# Sobel_FPGA_Block_1.net
KiCad netlist of a schematic drawn in Altium Designer
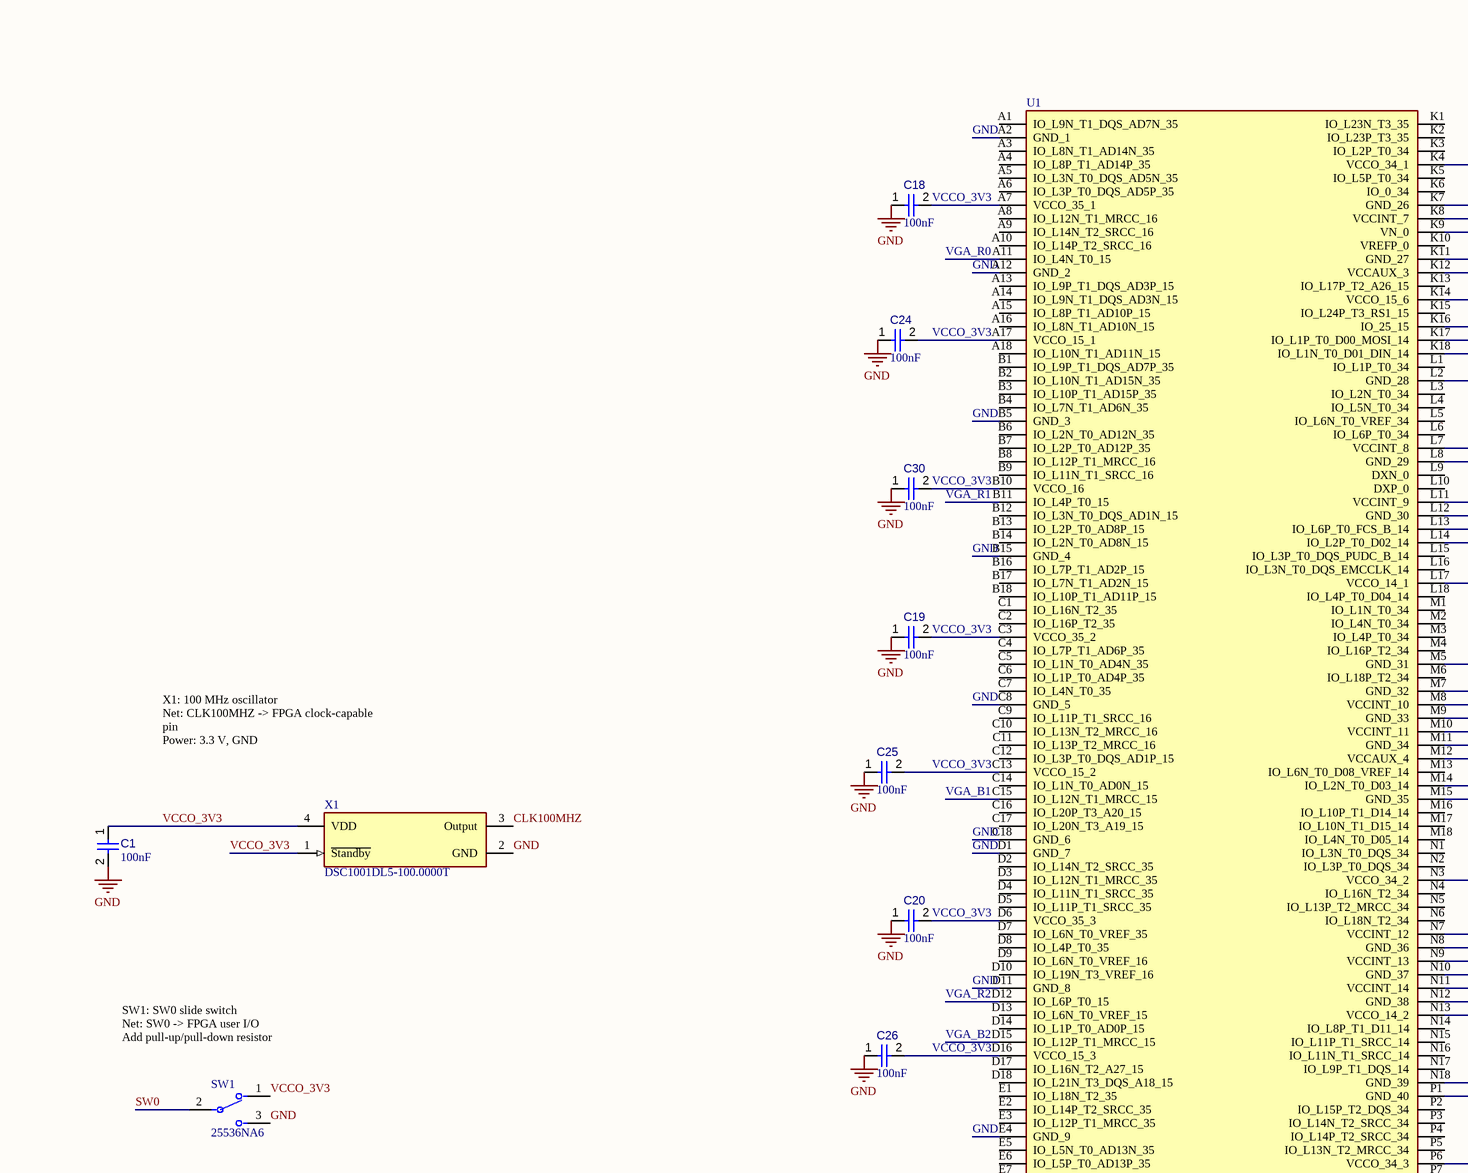
[diagram p0: Sobel_FPGA_Block (1).SchDoc, top left]
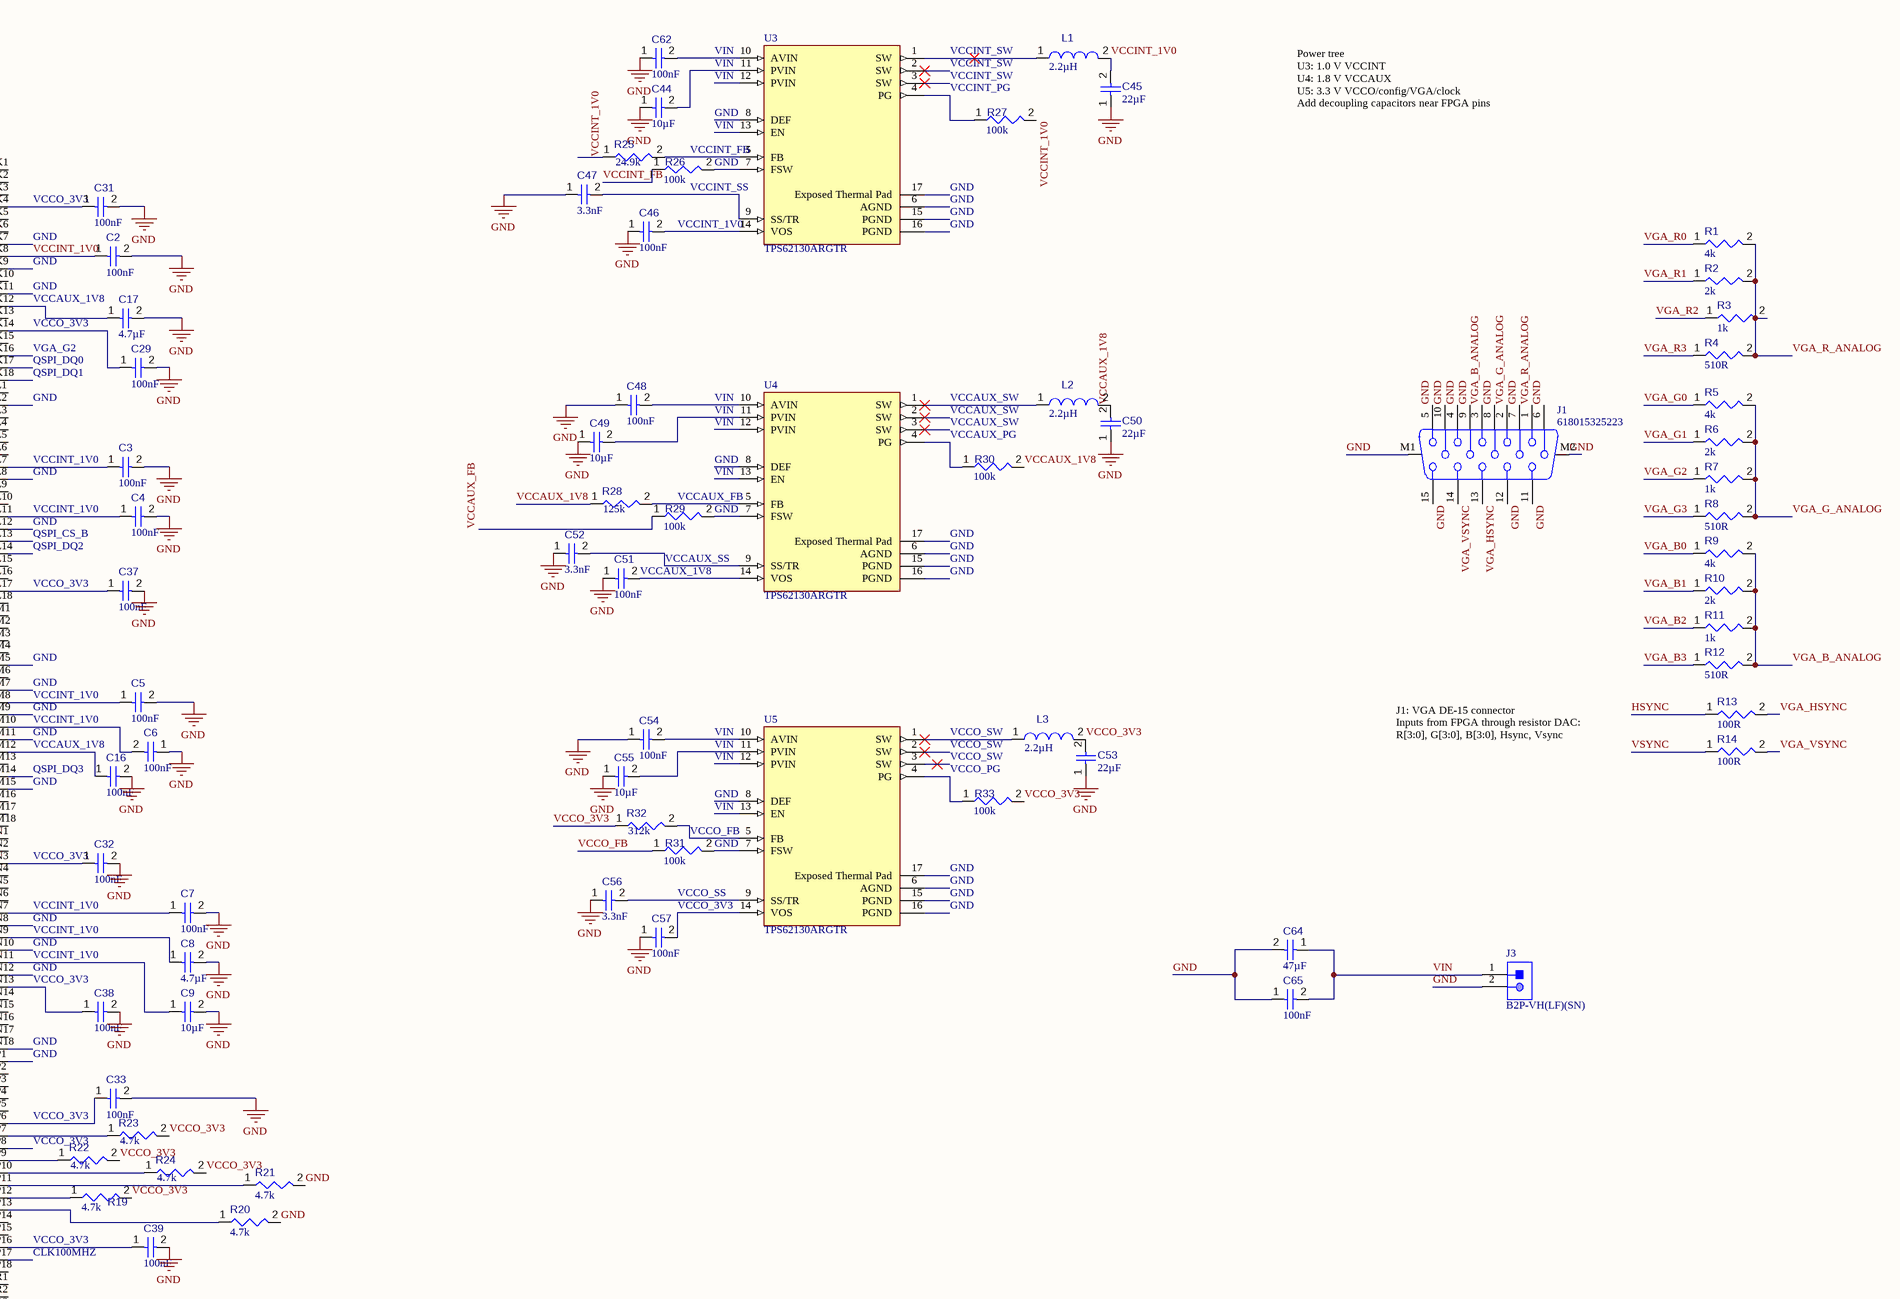
[diagram p1: Sobel_FPGA_Block (1).SchDoc, top right]
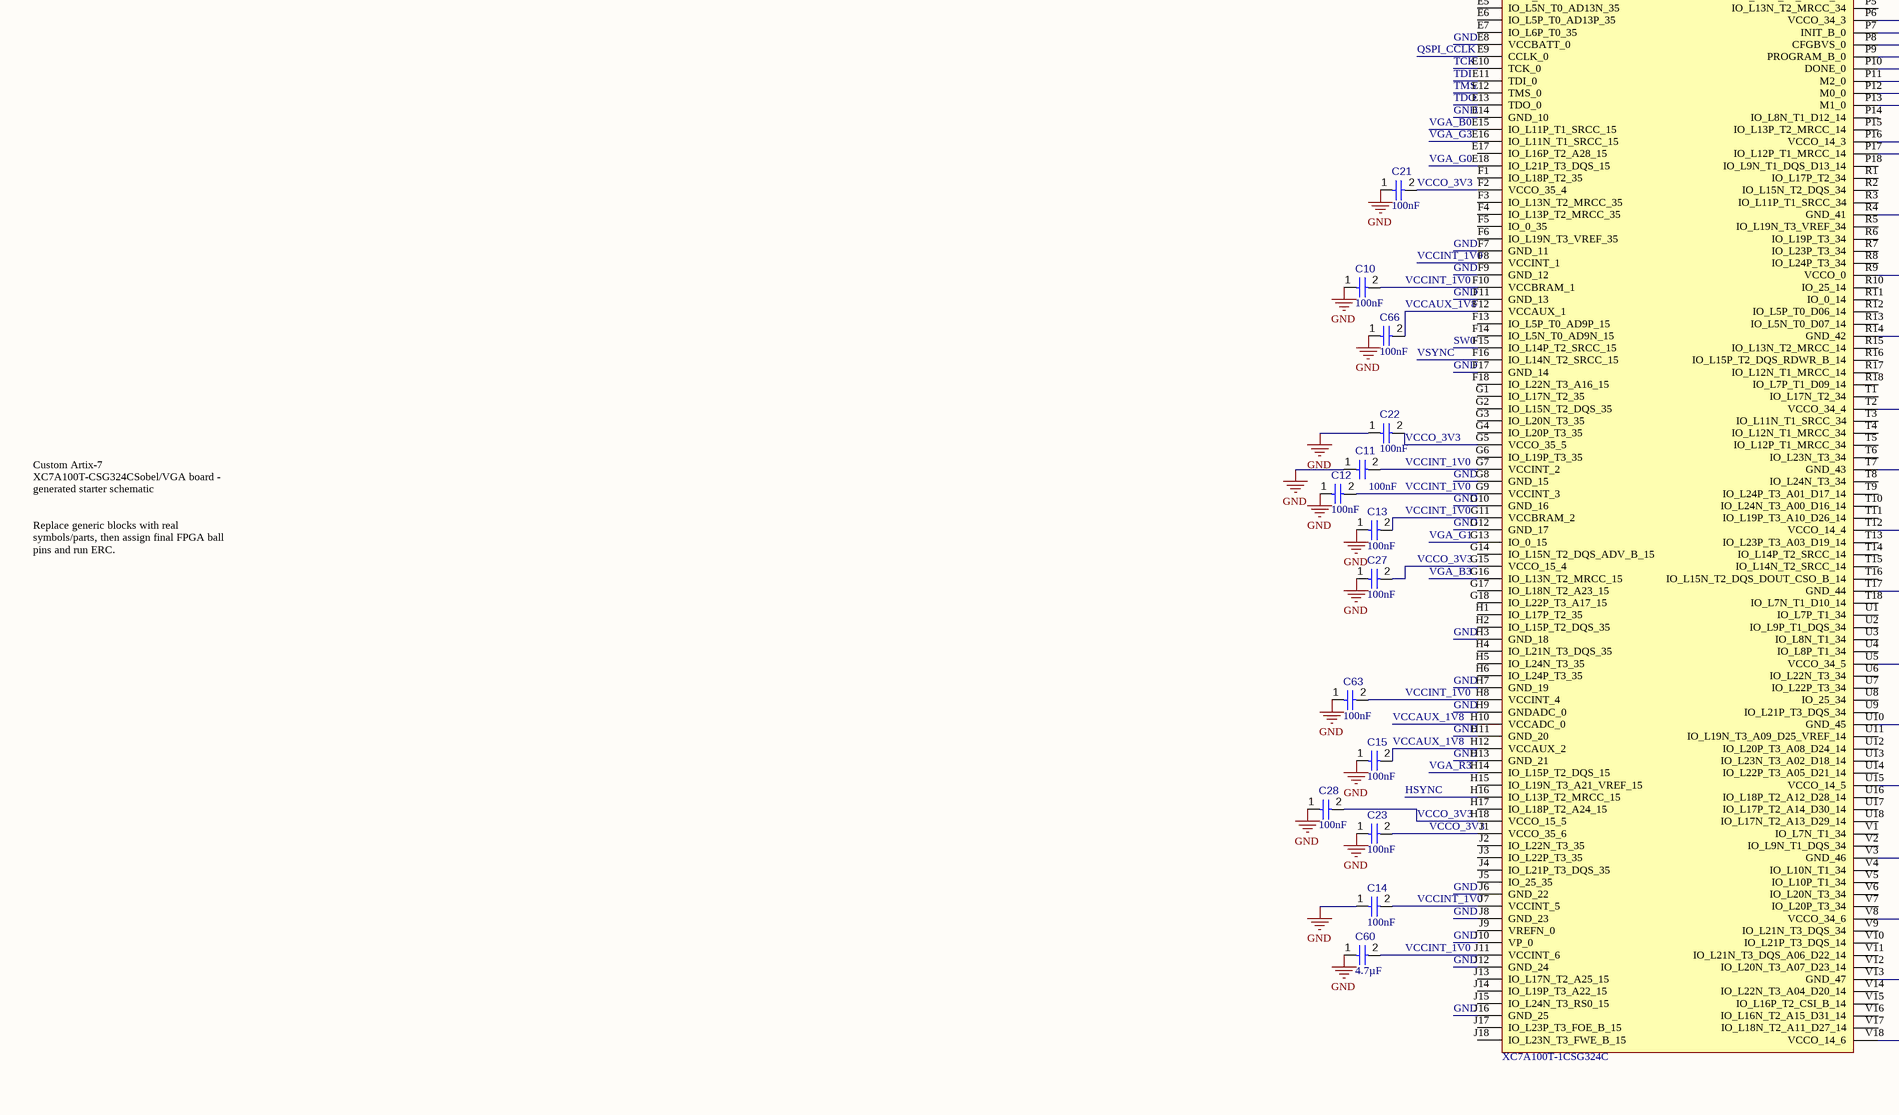
[diagram p2: Sobel_FPGA_Block (1).SchDoc, bottom left]
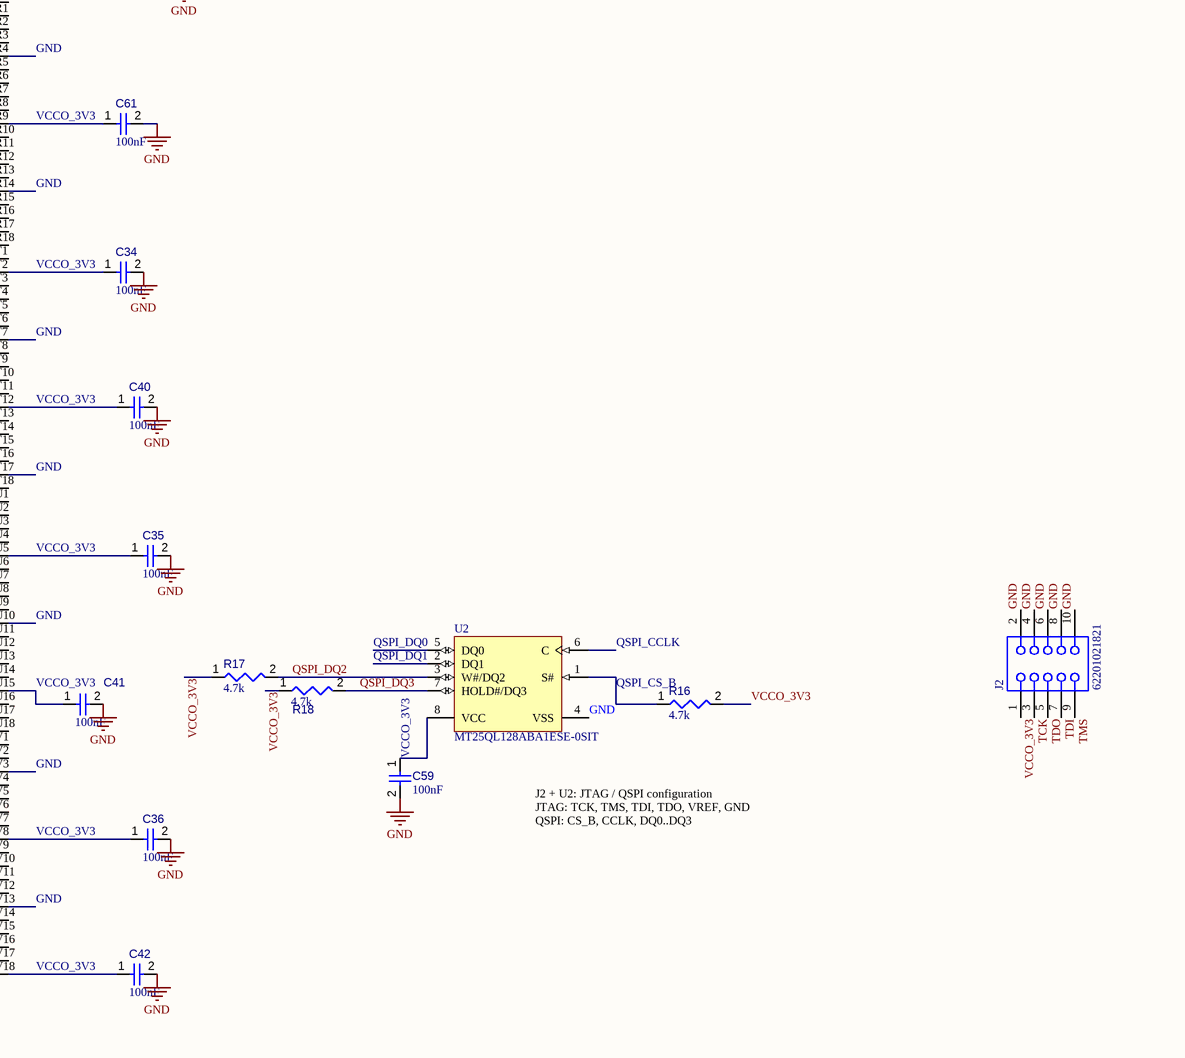
[diagram p3: Sobel_FPGA_Block (1).SchDoc, bottom right]

(export (version "E")
  (design (tool "Eeschema 10.0.6"))
  (components
    (comp (ref "C1")
      (value "100nF")
      (footprint "CAPC1005X56X25NL10T15")
      (description "Chip Capacitor, 6.8 nF, +/- 10%, 16 V, 0402 (1005 Metric)")
      (fields (field (name "TOLERANCE") "10%") (field (name "Comment") "Capacitor 6.8 nF +/- 10% 16 V 0402"))
      (libsource (lib "Turja Barua") (part "CAP-NP-2"))
    )
    (comp (ref "C2")
      (value "100nF")
      (footprint "CAPC1005X56X25NL10T15")
      (description "Chip Capacitor, 6.8 nF, +/- 10%, 16 V, 0402 (1005 Metric)")
      (fields (field (name "TOLERANCE") "10%") (field (name "Comment") "Capacitor 6.8 nF +/- 10% 16 V 0402"))
      (libsource (lib "Turja Barua") (part "CAP-NP-2"))
    )
    (comp (ref "C3")
      (value "100nF")
      (footprint "CAPC1005X56X25NL10T15")
      (description "Chip Capacitor, 6.8 nF, +/- 10%, 16 V, 0402 (1005 Metric)")
      (fields (field (name "TOLERANCE") "10%") (field (name "Comment") "Capacitor 6.8 nF +/- 10% 16 V 0402"))
      (libsource (lib "Turja Barua") (part "CAP-NP-2"))
    )
    (comp (ref "C4")
      (value "100nF")
      (footprint "CAPC1005X56X25NL10T15")
      (description "Chip Capacitor, 6.8 nF, +/- 10%, 16 V, 0402 (1005 Metric)")
      (fields (field (name "TOLERANCE") "10%") (field (name "Comment") "Capacitor 6.8 nF +/- 10% 16 V 0402"))
      (libsource (lib "Turja Barua") (part "CAP-NP-2"))
    )
    (comp (ref "C5")
      (value "100nF")
      (footprint "CAPC1005X56X25NL10T15")
      (description "Chip Capacitor, 6.8 nF, +/- 10%, 16 V, 0402 (1005 Metric)")
      (fields (field (name "TOLERANCE") "10%") (field (name "Comment") "Capacitor 6.8 nF +/- 10% 16 V 0402"))
      (libsource (lib "Turja Barua") (part "CAP-NP-2"))
    )
    (comp (ref "C6")
      (value "100nF")
      (footprint "CAPC1005X56X25NL10T15")
      (description "Chip Capacitor, 6.8 nF, +/- 10%, 16 V, 0402 (1005 Metric)")
      (fields (field (name "TOLERANCE") "10%") (field (name "Comment") "Capacitor 6.8 nF +/- 10% 16 V 0402"))
      (libsource (lib "Turja Barua") (part "CAP-NP-2"))
    )
    (comp (ref "C7")
      (value "100nF")
      (footprint "CAPC1005X56X25NL10T15")
      (description "Chip Capacitor, 6.8 nF, +/- 10%, 16 V, 0402 (1005 Metric)")
      (fields (field (name "TOLERANCE") "10%") (field (name "Comment") "Capacitor 6.8 nF +/- 10% 16 V 0402"))
      (libsource (lib "Turja Barua") (part "CAP-NP-2"))
    )
    (comp (ref "C8")
      (value "4.7µF")
      (footprint "CAPC3216X180X50NL20T25")
      (description "Chip Capacitor, 10 uF, +/- 10%, 16 V, 1206 (3216 Metric)")
      (fields (field (name "TOLERANCE") "10%") (field (name "Comment") "Capacitor 10 uF +/- 10% 16 V 1206"))
      (libsource (lib "Turja Barua") (part "CAP-NP-2"))
    )
    (comp (ref "C9")
      (value "10µF")
      (footprint "CAPC3216X180X50NL20T25")
      (description "Chip Capacitor, 10 uF, +/- 10%, 16 V, 1206 (3216 Metric)")
      (fields (field (name "TOLERANCE") "10%") (field (name "Comment") "Capacitor 10 uF +/- 10% 16 V 1206"))
      (libsource (lib "Turja Barua") (part "CAP-NP-2"))
    )
    (comp (ref "C10")
      (value "100nF")
      (footprint "CAPC1005X56X25NL10T15")
      (description "Chip Capacitor, 6.8 nF, +/- 10%, 16 V, 0402 (1005 Metric)")
      (fields (field (name "TOLERANCE") "10%") (field (name "Comment") "Capacitor 6.8 nF +/- 10% 16 V 0402"))
      (libsource (lib "Turja Barua") (part "CAP-NP-2"))
    )
    (comp (ref "C11")
      (value "100nF")
      (footprint "CAPC1005X56X25NL10T15")
      (description "Chip Capacitor, 6.8 nF, +/- 10%, 16 V, 0402 (1005 Metric)")
      (fields (field (name "TOLERANCE") "10%") (field (name "Comment") "Capacitor 6.8 nF +/- 10% 16 V 0402"))
      (libsource (lib "Turja Barua") (part "CAP-NP-2"))
    )
    (comp (ref "C12")
      (value "100nF")
      (footprint "CAPC1005X56X25NL10T15")
      (description "Chip Capacitor, 6.8 nF, +/- 10%, 16 V, 0402 (1005 Metric)")
      (fields (field (name "TOLERANCE") "10%") (field (name "Comment") "Capacitor 6.8 nF +/- 10% 16 V 0402"))
      (libsource (lib "Turja Barua") (part "CAP-NP-2"))
    )
    (comp (ref "C13")
      (value "100nF")
      (footprint "CAPC1005X56X25NL10T15")
      (description "Chip Capacitor, 6.8 nF, +/- 10%, 16 V, 0402 (1005 Metric)")
      (fields (field (name "TOLERANCE") "10%") (field (name "Comment") "Capacitor 6.8 nF +/- 10% 16 V 0402"))
      (libsource (lib "Turja Barua") (part "CAP-NP-2"))
    )
    (comp (ref "C14")
      (value "100nF")
      (footprint "CAPC1005X56X25NL10T15")
      (description "Chip Capacitor, 6.8 nF, +/- 10%, 16 V, 0402 (1005 Metric)")
      (fields (field (name "TOLERANCE") "10%") (field (name "Comment") "Capacitor 6.8 nF +/- 10% 16 V 0402"))
      (libsource (lib "Turja Barua") (part "CAP-NP-2"))
    )
    (comp (ref "C15")
      (value "100nF")
      (footprint "CAPC1005X56X25NL10T15")
      (description "Chip Capacitor, 6.8 nF, +/- 10%, 16 V, 0402 (1005 Metric)")
      (fields (field (name "TOLERANCE") "10%") (field (name "Comment") "Capacitor 6.8 nF +/- 10% 16 V 0402"))
      (libsource (lib "Turja Barua") (part "CAP-NP-2"))
    )
    (comp (ref "C16")
      (value "100nF")
      (footprint "CAPC1005X56X25NL10T15")
      (description "Chip Capacitor, 6.8 nF, +/- 10%, 16 V, 0402 (1005 Metric)")
      (fields (field (name "TOLERANCE") "10%") (field (name "Comment") "Capacitor 6.8 nF +/- 10% 16 V 0402"))
      (libsource (lib "Turja Barua") (part "CAP-NP-2"))
    )
    (comp (ref "C17")
      (value "4.7µF")
      (footprint "CAPC3216X180X50NL20T25")
      (description "Chip Capacitor, 10 uF, +/- 10%, 16 V, 1206 (3216 Metric)")
      (fields (field (name "TOLERANCE") "10%") (field (name "Comment") "Capacitor 10 uF +/- 10% 16 V 1206"))
      (libsource (lib "Turja Barua") (part "CAP-NP-2"))
    )
    (comp (ref "C18")
      (value "100nF")
      (footprint "CAPC1005X56X25NL10T15")
      (description "Chip Capacitor, 6.8 nF, +/- 10%, 16 V, 0402 (1005 Metric)")
      (fields (field (name "TOLERANCE") "10%") (field (name "Comment") "Capacitor 6.8 nF +/- 10% 16 V 0402"))
      (libsource (lib "Turja Barua") (part "CAP-NP-2"))
    )
    (comp (ref "C19")
      (value "100nF")
      (footprint "CAPC1005X56X25NL10T15")
      (description "Chip Capacitor, 6.8 nF, +/- 10%, 16 V, 0402 (1005 Metric)")
      (fields (field (name "TOLERANCE") "10%") (field (name "Comment") "Capacitor 6.8 nF +/- 10% 16 V 0402"))
      (libsource (lib "Turja Barua") (part "CAP-NP-2"))
    )
    (comp (ref "C20")
      (value "100nF")
      (footprint "CAPC1005X56X25NL10T15")
      (description "Chip Capacitor, 6.8 nF, +/- 10%, 16 V, 0402 (1005 Metric)")
      (fields (field (name "TOLERANCE") "10%") (field (name "Comment") "Capacitor 6.8 nF +/- 10% 16 V 0402"))
      (libsource (lib "Turja Barua") (part "CAP-NP-2"))
    )
    (comp (ref "C21")
      (value "100nF")
      (footprint "CAPC1005X56X25NL10T15")
      (description "Chip Capacitor, 6.8 nF, +/- 10%, 16 V, 0402 (1005 Metric)")
      (fields (field (name "TOLERANCE") "10%") (field (name "Comment") "Capacitor 6.8 nF +/- 10% 16 V 0402"))
      (libsource (lib "Turja Barua") (part "CAP-NP-2"))
    )
    (comp (ref "C22")
      (value "100nF")
      (footprint "CAPC1005X56X25NL10T15")
      (description "Chip Capacitor, 6.8 nF, +/- 10%, 16 V, 0402 (1005 Metric)")
      (fields (field (name "TOLERANCE") "10%") (field (name "Comment") "Capacitor 6.8 nF +/- 10% 16 V 0402"))
      (libsource (lib "Turja Barua") (part "CAP-NP-2"))
    )
    (comp (ref "C23")
      (value "100nF")
      (footprint "CAPC1005X56X25NL10T15")
      (description "Chip Capacitor, 6.8 nF, +/- 10%, 16 V, 0402 (1005 Metric)")
      (fields (field (name "TOLERANCE") "10%") (field (name "Comment") "Capacitor 6.8 nF +/- 10% 16 V 0402"))
      (libsource (lib "Turja Barua") (part "CAP-NP-2"))
    )
    (comp (ref "C24")
      (value "100nF")
      (footprint "CAPC1005X56X25NL10T15")
      (description "Chip Capacitor, 6.8 nF, +/- 10%, 16 V, 0402 (1005 Metric)")
      (fields (field (name "TOLERANCE") "10%") (field (name "Comment") "Capacitor 6.8 nF +/- 10% 16 V 0402"))
      (libsource (lib "Turja Barua") (part "CAP-NP-2"))
    )
    (comp (ref "C25")
      (value "100nF")
      (footprint "CAPC1005X56X25NL10T15")
      (description "Chip Capacitor, 6.8 nF, +/- 10%, 16 V, 0402 (1005 Metric)")
      (fields (field (name "TOLERANCE") "10%") (field (name "Comment") "Capacitor 6.8 nF +/- 10% 16 V 0402"))
      (libsource (lib "Turja Barua") (part "CAP-NP-2"))
    )
    (comp (ref "C26")
      (value "100nF")
      (footprint "CAPC1005X56X25NL10T15")
      (description "Chip Capacitor, 6.8 nF, +/- 10%, 16 V, 0402 (1005 Metric)")
      (fields (field (name "TOLERANCE") "10%") (field (name "Comment") "Capacitor 6.8 nF +/- 10% 16 V 0402"))
      (libsource (lib "Turja Barua") (part "CAP-NP-2"))
    )
    (comp (ref "C27")
      (value "100nF")
      (footprint "CAPC1005X56X25NL10T15")
      (description "Chip Capacitor, 6.8 nF, +/- 10%, 16 V, 0402 (1005 Metric)")
      (fields (field (name "TOLERANCE") "10%") (field (name "Comment") "Capacitor 6.8 nF +/- 10% 16 V 0402"))
      (libsource (lib "Turja Barua") (part "CAP-NP-2"))
    )
    (comp (ref "C28")
      (value "100nF")
      (footprint "CAPC1005X56X25NL10T15")
      (description "Chip Capacitor, 6.8 nF, +/- 10%, 16 V, 0402 (1005 Metric)")
      (fields (field (name "TOLERANCE") "10%") (field (name "Comment") "Capacitor 6.8 nF +/- 10% 16 V 0402"))
      (libsource (lib "Turja Barua") (part "CAP-NP-2"))
    )
    (comp (ref "C29")
      (value "100nF")
      (footprint "CAPC1005X56X25NL10T15")
      (description "Chip Capacitor, 6.8 nF, +/- 10%, 16 V, 0402 (1005 Metric)")
      (fields (field (name "TOLERANCE") "10%") (field (name "Comment") "Capacitor 6.8 nF +/- 10% 16 V 0402"))
      (libsource (lib "Turja Barua") (part "CAP-NP-2"))
    )
    (comp (ref "C30")
      (value "100nF")
      (footprint "CAPC1005X56X25NL10T15")
      (description "Chip Capacitor, 6.8 nF, +/- 10%, 16 V, 0402 (1005 Metric)")
      (fields (field (name "TOLERANCE") "10%") (field (name "Comment") "Capacitor 6.8 nF +/- 10% 16 V 0402"))
      (libsource (lib "Turja Barua") (part "CAP-NP-2"))
    )
    (comp (ref "C31")
      (value "100nF")
      (footprint "CAPC1005X56X25NL10T15")
      (description "Chip Capacitor, 6.8 nF, +/- 10%, 16 V, 0402 (1005 Metric)")
      (fields (field (name "TOLERANCE") "10%") (field (name "Comment") "Capacitor 6.8 nF +/- 10% 16 V 0402"))
      (libsource (lib "Turja Barua") (part "CAP-NP-2"))
    )
    (comp (ref "C32")
      (value "100nF")
      (footprint "CAPC1005X56X25NL10T15")
      (description "Chip Capacitor, 6.8 nF, +/- 10%, 16 V, 0402 (1005 Metric)")
      (fields (field (name "TOLERANCE") "10%") (field (name "Comment") "Capacitor 6.8 nF +/- 10% 16 V 0402"))
      (libsource (lib "Turja Barua") (part "CAP-NP-2"))
    )
    (comp (ref "C33")
      (value "100nF")
      (footprint "CAPC1005X56X25NL10T15")
      (description "Chip Capacitor, 6.8 nF, +/- 10%, 16 V, 0402 (1005 Metric)")
      (fields (field (name "TOLERANCE") "10%") (field (name "Comment") "Capacitor 6.8 nF +/- 10% 16 V 0402"))
      (libsource (lib "Turja Barua") (part "CAP-NP-2"))
    )
    (comp (ref "C34")
      (value "100nF")
      (footprint "CAPC1005X56X25NL10T15")
      (description "Chip Capacitor, 6.8 nF, +/- 10%, 16 V, 0402 (1005 Metric)")
      (fields (field (name "TOLERANCE") "10%") (field (name "Comment") "Capacitor 6.8 nF +/- 10% 16 V 0402"))
      (libsource (lib "Turja Barua") (part "CAP-NP-2"))
    )
    (comp (ref "C35")
      (value "100nF")
      (footprint "CAPC1005X56X25NL10T15")
      (description "Chip Capacitor, 6.8 nF, +/- 10%, 16 V, 0402 (1005 Metric)")
      (fields (field (name "TOLERANCE") "10%") (field (name "Comment") "Capacitor 6.8 nF +/- 10% 16 V 0402"))
      (libsource (lib "Turja Barua") (part "CAP-NP-2"))
    )
    (comp (ref "C36")
      (value "100nF")
      (footprint "CAPC1005X56X25NL10T15")
      (description "Chip Capacitor, 6.8 nF, +/- 10%, 16 V, 0402 (1005 Metric)")
      (fields (field (name "TOLERANCE") "10%") (field (name "Comment") "Capacitor 6.8 nF +/- 10% 16 V 0402"))
      (libsource (lib "Turja Barua") (part "CAP-NP-2"))
    )
    (comp (ref "C37")
      (value "100nF")
      (footprint "CAPC1005X56X25NL10T15")
      (description "Chip Capacitor, 6.8 nF, +/- 10%, 16 V, 0402 (1005 Metric)")
      (fields (field (name "TOLERANCE") "10%") (field (name "Comment") "Capacitor 6.8 nF +/- 10% 16 V 0402"))
      (libsource (lib "Turja Barua") (part "CAP-NP-2"))
    )
    (comp (ref "C38")
      (value "100nF")
      (footprint "CAPC1005X56X25NL10T15")
      (description "Chip Capacitor, 6.8 nF, +/- 10%, 16 V, 0402 (1005 Metric)")
      (fields (field (name "TOLERANCE") "10%") (field (name "Comment") "Capacitor 6.8 nF +/- 10% 16 V 0402"))
      (libsource (lib "Turja Barua") (part "CAP-NP-2"))
    )
    (comp (ref "C39")
      (value "100nF")
      (footprint "CAPC1005X56X25NL10T15")
      (description "Chip Capacitor, 6.8 nF, +/- 10%, 16 V, 0402 (1005 Metric)")
      (fields (field (name "TOLERANCE") "10%") (field (name "Comment") "Capacitor 6.8 nF +/- 10% 16 V 0402"))
      (libsource (lib "Turja Barua") (part "CAP-NP-2"))
    )
    (comp (ref "C40")
      (value "100nF")
      (footprint "CAPC1005X56X25NL10T15")
      (description "Chip Capacitor, 6.8 nF, +/- 10%, 16 V, 0402 (1005 Metric)")
      (fields (field (name "TOLERANCE") "10%") (field (name "Comment") "Capacitor 6.8 nF +/- 10% 16 V 0402"))
      (libsource (lib "Turja Barua") (part "CAP-NP-2"))
    )
    (comp (ref "C41")
      (value "100nF")
      (footprint "CAPC1005X56X25NL10T15")
      (description "Chip Capacitor, 6.8 nF, +/- 10%, 16 V, 0402 (1005 Metric)")
      (fields (field (name "TOLERANCE") "10%") (field (name "Comment") "Capacitor 6.8 nF +/- 10% 16 V 0402"))
      (libsource (lib "Turja Barua") (part "CAP-NP-2"))
    )
    (comp (ref "C42")
      (value "100nF")
      (footprint "CAPC1005X56X25NL10T15")
      (description "Chip Capacitor, 6.8 nF, +/- 10%, 16 V, 0402 (1005 Metric)")
      (fields (field (name "TOLERANCE") "10%") (field (name "Comment") "Capacitor 6.8 nF +/- 10% 16 V 0402"))
      (libsource (lib "Turja Barua") (part "CAP-NP-2"))
    )
    (comp (ref "C44")
      (value "10µF")
      (footprint "CAPC3216X180X50NL20T25")
      (description "Chip Capacitor, 10 uF, +/- 10%, 16 V, 1206 (3216 Metric)")
      (fields (field (name "TOLERANCE") "10%") (field (name "Comment") "Capacitor 10 uF +/- 10% 16 V 1206"))
      (libsource (lib "Turja Barua") (part "CAP-NP-2"))
    )
    (comp (ref "C45")
      (value "22µF")
      (footprint "CAPC3216X180X50NL20T25")
      (description "Chip Capacitor, 10 uF, +/- 10%, 16 V, 1206 (3216 Metric)")
      (fields (field (name "TOLERANCE") "10%") (field (name "Comment") "Capacitor 10 uF +/- 10% 16 V 1206"))
      (libsource (lib "Turja Barua") (part "CAP-NP-2"))
    )
    (comp (ref "C46")
      (value "100nF")
      (footprint "CAPC1005X56X25NL10T15")
      (description "Chip Capacitor, 6.8 nF, +/- 10%, 16 V, 0402 (1005 Metric)")
      (fields (field (name "TOLERANCE") "10%") (field (name "Comment") "Capacitor 6.8 nF +/- 10% 16 V 0402"))
      (libsource (lib "Turja Barua") (part "CAP-NP-2"))
    )
    (comp (ref "C47")
      (value "3.3nF")
      (footprint "CAPC1005X56X25NL10T15")
      (description "Chip Capacitor, 6.8 nF, +/- 10%, 16 V, 0402 (1005 Metric)")
      (fields (field (name "TOLERANCE") "10%") (field (name "Comment") "Capacitor 6.8 nF +/- 10% 16 V 0402"))
      (libsource (lib "Turja Barua") (part "CAP-NP-2"))
    )
    (comp (ref "C48")
      (value "100nF")
      (footprint "CAPC1005X56X25NL10T15")
      (description "Chip Capacitor, 6.8 nF, +/- 10%, 16 V, 0402 (1005 Metric)")
      (fields (field (name "TOLERANCE") "10%") (field (name "Comment") "Capacitor 6.8 nF +/- 10% 16 V 0402"))
      (libsource (lib "Turja Barua") (part "CAP-NP-2"))
    )
    (comp (ref "C49")
      (value "10µF")
      (footprint "CAPC3216X180X50NL20T25")
      (description "Chip Capacitor, 10 uF, +/- 10%, 16 V, 1206 (3216 Metric)")
      (fields (field (name "TOLERANCE") "10%") (field (name "Comment") "Capacitor 10 uF +/- 10% 16 V 1206"))
      (libsource (lib "Turja Barua") (part "CAP-NP-2"))
    )
    (comp (ref "C50")
      (value "22µF")
      (footprint "CAPC3216X180X50NL20T25")
      (description "Chip Capacitor, 10 uF, +/- 10%, 16 V, 1206 (3216 Metric)")
      (fields (field (name "TOLERANCE") "10%") (field (name "Comment") "Capacitor 10 uF +/- 10% 16 V 1206"))
      (libsource (lib "Turja Barua") (part "CAP-NP-2"))
    )
    (comp (ref "C51")
      (value "100nF")
      (footprint "CAPC1005X56X25NL10T15")
      (description "Chip Capacitor, 6.8 nF, +/- 10%, 16 V, 0402 (1005 Metric)")
      (fields (field (name "TOLERANCE") "10%") (field (name "Comment") "Capacitor 6.8 nF +/- 10% 16 V 0402"))
      (libsource (lib "Turja Barua") (part "CAP-NP-2"))
    )
    (comp (ref "C52")
      (value "3.3nF")
      (footprint "CAPC1005X56X25NL10T15")
      (description "Chip Capacitor, 6.8 nF, +/- 10%, 16 V, 0402 (1005 Metric)")
      (fields (field (name "TOLERANCE") "10%") (field (name "Comment") "Capacitor 6.8 nF +/- 10% 16 V 0402"))
      (libsource (lib "Turja Barua") (part "CAP-NP-2"))
    )
    (comp (ref "C53")
      (value "22µF")
      (footprint "CAPC3216X180X50NL20T25")
      (description "Chip Capacitor, 10 uF, +/- 10%, 16 V, 1206 (3216 Metric)")
      (fields (field (name "TOLERANCE") "10%") (field (name "Comment") "Capacitor 10 uF +/- 10% 16 V 1206"))
      (libsource (lib "Turja Barua") (part "CAP-NP-2"))
    )
    (comp (ref "C54")
      (value "100nF")
      (footprint "CAPC1005X56X25NL10T15")
      (description "Chip Capacitor, 6.8 nF, +/- 10%, 16 V, 0402 (1005 Metric)")
      (fields (field (name "TOLERANCE") "10%") (field (name "Comment") "Capacitor 6.8 nF +/- 10% 16 V 0402"))
      (libsource (lib "Turja Barua") (part "CAP-NP-2"))
    )
    (comp (ref "C55")
      (value "10µF")
      (footprint "CAPC3216X180X50NL20T25")
      (description "Chip Capacitor, 10 uF, +/- 10%, 16 V, 1206 (3216 Metric)")
      (fields (field (name "TOLERANCE") "10%") (field (name "Comment") "Capacitor 10 uF +/- 10% 16 V 1206"))
      (libsource (lib "Turja Barua") (part "CAP-NP-2"))
    )
    (comp (ref "C56")
      (value "3.3nF")
      (footprint "CAPC1005X56X25NL10T15")
      (description "Chip Capacitor, 6.8 nF, +/- 10%, 16 V, 0402 (1005 Metric)")
      (fields (field (name "TOLERANCE") "10%") (field (name "Comment") "Capacitor 6.8 nF +/- 10% 16 V 0402"))
      (libsource (lib "Turja Barua") (part "CAP-NP-2"))
    )
    (comp (ref "C57")
      (value "100nF")
      (footprint "CAPC1005X56X25NL10T15")
      (description "Chip Capacitor, 6.8 nF, +/- 10%, 16 V, 0402 (1005 Metric)")
      (fields (field (name "TOLERANCE") "10%") (field (name "Comment") "Capacitor 6.8 nF +/- 10% 16 V 0402"))
      (libsource (lib "Turja Barua") (part "CAP-NP-2"))
    )
    (comp (ref "C59")
      (value "100nF")
      (footprint "CAPC1005X56X25NL10T15")
      (description "Chip Capacitor, 6.8 nF, +/- 10%, 16 V, 0402 (1005 Metric)")
      (fields (field (name "TOLERANCE") "10%") (field (name "Comment") "Capacitor 6.8 nF +/- 10% 16 V 0402"))
      (libsource (lib "Turja Barua") (part "CAP-NP-2"))
    )
    (comp (ref "C60")
      (value "4.7µF")
      (footprint "CAPC3216X180X50NL20T25")
      (description "Chip Capacitor, 10 uF, +/- 10%, 16 V, 1206 (3216 Metric)")
      (fields (field (name "TOLERANCE") "10%") (field (name "Comment") "Capacitor 10 uF +/- 10% 16 V 1206"))
      (libsource (lib "Turja Barua") (part "CAP-NP-2"))
    )
    (comp (ref "C61")
      (value "100nF")
      (footprint "CAPC1005X56X25NL10T15")
      (description "Chip Capacitor, 6.8 nF, +/- 10%, 16 V, 0402 (1005 Metric)")
      (fields (field (name "TOLERANCE") "10%") (field (name "Comment") "Capacitor 6.8 nF +/- 10% 16 V 0402"))
      (libsource (lib "Turja Barua") (part "CAP-NP-2"))
    )
    (comp (ref "C62")
      (value "100nF")
      (footprint "CAPC1005X56X25NL10T15")
      (description "Chip Capacitor, 6.8 nF, +/- 10%, 16 V, 0402 (1005 Metric)")
      (fields (field (name "TOLERANCE") "10%") (field (name "Comment") "Capacitor 6.8 nF +/- 10% 16 V 0402"))
      (libsource (lib "Turja Barua") (part "CAP-NP-2"))
    )
    (comp (ref "C63")
      (value "100nF")
      (footprint "CAPC1005X56X25NL10T15")
      (description "Chip Capacitor, 6.8 nF, +/- 10%, 16 V, 0402 (1005 Metric)")
      (fields (field (name "TOLERANCE") "10%") (field (name "Comment") "Capacitor 6.8 nF +/- 10% 16 V 0402"))
      (libsource (lib "Turja Barua") (part "CAP-NP-2"))
    )
    (comp (ref "C64")
      (value "47µF")
      (footprint "CAPC3216X180X50NL20T25")
      (description "Chip Capacitor, 10 uF, +/- 10%, 16 V, 1206 (3216 Metric)")
      (fields (field (name "TOLERANCE") "10%") (field (name "Comment") "Capacitor 10 uF +/- 10% 16 V 1206"))
      (libsource (lib "Turja Barua") (part "CAP-NP-2"))
    )
    (comp (ref "C65")
      (value "100nF")
      (footprint "CAPC1005X56X25NL10T15")
      (description "Chip Capacitor, 6.8 nF, +/- 10%, 16 V, 0402 (1005 Metric)")
      (fields (field (name "TOLERANCE") "10%") (field (name "Comment") "Capacitor 6.8 nF +/- 10% 16 V 0402"))
      (libsource (lib "Turja Barua") (part "CAP-NP-2"))
    )
    (comp (ref "C66")
      (value "100nF")
      (footprint "CAPC1005X56X25NL10T15")
      (description "Chip Capacitor, 6.8 nF, +/- 10%, 16 V, 0402 (1005 Metric)")
      (fields (field (name "TOLERANCE") "10%") (field (name "Comment") "Capacitor 6.8 nF +/- 10% 16 V 0402"))
      (libsource (lib "Turja Barua") (part "CAP-NP-2"))
    )
    (comp (ref "J1")
      (value "618015325223")
      (footprint "618015325223")
      (description "Hd-D Sub Conn, R/A Rcpt, 15Pos, De, Tht Rohs Compliant: Yes")
      (libsource (lib "Turja Barua") (part "D-Sub_Female_15p_High Density"))
    )
    (comp (ref "J2")
      (value "62201021821")
      (footprint "62201021821")
      (description "Connector Header Surface Mount 10 position 0.050\" (1.27mm)-JTAG Connector")
      (libsource (lib "Turja Barua") (part "Header_Female_2R_10P"))
    )
    (comp (ref "J3")
      (value "B2P-VH(LF)(SN)")
      (footprint "JST-B2P-VH(LF)(SN)_V")
      (fields (field (name "MANUFACTURER") "JST"))
      (libsource (lib "Turja Barua") (part "CN-1P-M-R2"))
    )
    (comp (ref "L1")
      (value "2.2µH")
      (footprint "SUSUMU-PCMB063T_V")
      (description "Shielded Wirewound Inductor, 2.2 uH, +/- 20%, -20 to 120 degC, 2-Pin SMD, RoHS, Tape and Reel")
      (fields (field (name "TOLERANCE") "20%") (field (name "Comment") "PCMB063T-2R2MS"))
      (libsource (lib "Turja Barua") (part "CMP-001-0020-1"))
    )
    (comp (ref "L2")
      (value "2.2µH")
      (footprint "SUSUMU-PCMB063T_V")
      (description "Shielded Wirewound Inductor, 2.2 uH, +/- 20%, -20 to 120 degC, 2-Pin SMD, RoHS, Tape and Reel")
      (fields (field (name "TOLERANCE") "20%") (field (name "Comment") "PCMB063T-2R2MS"))
      (libsource (lib "Turja Barua") (part "CMP-001-0020-1"))
    )
    (comp (ref "L3")
      (value "2.2µH")
      (footprint "SUSUMU-PCMB063T_V")
      (description "Shielded Wirewound Inductor, 2.2 uH, +/- 20%, -20 to 120 degC, 2-Pin SMD, RoHS, Tape and Reel")
      (fields (field (name "TOLERANCE") "20%") (field (name "Comment") "PCMB063T-2R2MS"))
      (libsource (lib "Turja Barua") (part "CMP-001-0020-1"))
    )
    (comp (ref "R1")
      (value "4k")
      (footprint "RESA60-630X240")
      (description "Axial Resistor, 475 Ohm, +/- 1%, 0.25 W, -55 to 155 degC, 2-Pin THD, RoHS, Bulk")
      (fields (field (name "MANUFACTURER") "Yageo") (field (name "TOLERANCE") "1%"))
      (libsource (lib "Turja Barua") (part "RES-2"))
    )
    (comp (ref "R2")
      (value "2k")
      (footprint "RESA60-630X240")
      (description "Axial Resistor, 475 Ohm, +/- 1%, 0.25 W, -55 to 155 degC, 2-Pin THD, RoHS, Bulk")
      (fields (field (name "MANUFACTURER") "Yageo") (field (name "TOLERANCE") "1%"))
      (libsource (lib "Turja Barua") (part "RES-2"))
    )
    (comp (ref "R3")
      (value "1k")
      (footprint "RESA60-630X240")
      (description "Axial Resistor, 475 Ohm, +/- 1%, 0.25 W, -55 to 155 degC, 2-Pin THD, RoHS, Bulk")
      (fields (field (name "MANUFACTURER") "Yageo") (field (name "TOLERANCE") "1%"))
      (libsource (lib "Turja Barua") (part "RES-2"))
    )
    (comp (ref "R4")
      (value "510R")
      (footprint "RESA60-630X240")
      (description "Axial Resistor, 475 Ohm, +/- 1%, 0.25 W, -55 to 155 degC, 2-Pin THD, RoHS, Bulk")
      (fields (field (name "MANUFACTURER") "Yageo") (field (name "TOLERANCE") "1%"))
      (libsource (lib "Turja Barua") (part "RES-2"))
    )
    (comp (ref "R5")
      (value "4k")
      (footprint "RESA60-630X240")
      (description "Axial Resistor, 475 Ohm, +/- 1%, 0.25 W, -55 to 155 degC, 2-Pin THD, RoHS, Bulk")
      (fields (field (name "MANUFACTURER") "Yageo") (field (name "TOLERANCE") "1%"))
      (libsource (lib "Turja Barua") (part "RES-2"))
    )
    (comp (ref "R6")
      (value "2k")
      (footprint "RESA60-630X240")
      (description "Axial Resistor, 475 Ohm, +/- 1%, 0.25 W, -55 to 155 degC, 2-Pin THD, RoHS, Bulk")
      (fields (field (name "MANUFACTURER") "Yageo") (field (name "TOLERANCE") "1%"))
      (libsource (lib "Turja Barua") (part "RES-2"))
    )
    (comp (ref "R7")
      (value "1k")
      (footprint "RESA60-630X240")
      (description "Axial Resistor, 475 Ohm, +/- 1%, 0.25 W, -55 to 155 degC, 2-Pin THD, RoHS, Bulk")
      (fields (field (name "MANUFACTURER") "Yageo") (field (name "TOLERANCE") "1%"))
      (libsource (lib "Turja Barua") (part "RES-2"))
    )
    (comp (ref "R8")
      (value "510R")
      (footprint "RESA60-630X240")
      (description "Axial Resistor, 475 Ohm, +/- 1%, 0.25 W, -55 to 155 degC, 2-Pin THD, RoHS, Bulk")
      (fields (field (name "MANUFACTURER") "Yageo") (field (name "TOLERANCE") "1%"))
      (libsource (lib "Turja Barua") (part "RES-2"))
    )
    (comp (ref "R9")
      (value "4k")
      (footprint "RESA60-630X240")
      (description "Axial Resistor, 475 Ohm, +/- 1%, 0.25 W, -55 to 155 degC, 2-Pin THD, RoHS, Bulk")
      (fields (field (name "MANUFACTURER") "Yageo") (field (name "TOLERANCE") "1%"))
      (libsource (lib "Turja Barua") (part "RES-2"))
    )
    (comp (ref "R10")
      (value "2k")
      (footprint "RESA60-630X240")
      (description "Axial Resistor, 475 Ohm, +/- 1%, 0.25 W, -55 to 155 degC, 2-Pin THD, RoHS, Bulk")
      (fields (field (name "MANUFACTURER") "Yageo") (field (name "TOLERANCE") "1%"))
      (libsource (lib "Turja Barua") (part "RES-2"))
    )
    (comp (ref "R11")
      (value "1k")
      (footprint "RESA60-630X240")
      (description "Axial Resistor, 475 Ohm, +/- 1%, 0.25 W, -55 to 155 degC, 2-Pin THD, RoHS, Bulk")
      (fields (field (name "MANUFACTURER") "Yageo") (field (name "TOLERANCE") "1%"))
      (libsource (lib "Turja Barua") (part "RES-2"))
    )
    (comp (ref "R12")
      (value "510R")
      (footprint "RESA60-630X240")
      (description "Axial Resistor, 475 Ohm, +/- 1%, 0.25 W, -55 to 155 degC, 2-Pin THD, RoHS, Bulk")
      (fields (field (name "MANUFACTURER") "Yageo") (field (name "TOLERANCE") "1%"))
      (libsource (lib "Turja Barua") (part "RES-2"))
    )
    (comp (ref "R13")
      (value "100R")
      (footprint "RESA60-630X240")
      (description "Axial Resistor, 475 Ohm, +/- 1%, 0.25 W, -55 to 155 degC, 2-Pin THD, RoHS, Bulk")
      (fields (field (name "MANUFACTURER") "Yageo") (field (name "TOLERANCE") "1%"))
      (libsource (lib "Turja Barua") (part "RES-2"))
    )
    (comp (ref "R14")
      (value "100R")
      (footprint "RESA60-630X240")
      (description "Axial Resistor, 475 Ohm, +/- 1%, 0.25 W, -55 to 155 degC, 2-Pin THD, RoHS, Bulk")
      (fields (field (name "MANUFACTURER") "Yageo") (field (name "TOLERANCE") "1%"))
      (libsource (lib "Turja Barua") (part "RES-2"))
    )
    (comp (ref "R16")
      (value "4.7k")
      (footprint "RESC0402(1005)_L")
      (description "84K5 0.063W 1% 0402 (1005 Metric)  SMD")
      (fields (field (name "POWER") "63mW") (field (name "TOLERANCE") "1%"))
      (libsource (lib "Turja Barua") (part "84D5KR2F"))
    )
    (comp (ref "R17")
      (value "4.7k")
      (footprint "RESC0402(1005)_L")
      (description "84K5 0.063W 1% 0402 (1005 Metric)  SMD")
      (fields (field (name "POWER") "63mW") (field (name "TOLERANCE") "1%"))
      (libsource (lib "Turja Barua") (part "84D5KR2F"))
    )
    (comp (ref "R18")
      (value "4.7k")
      (footprint "RESC0402(1005)_L")
      (description "84K5 0.063W 1% 0402 (1005 Metric)  SMD")
      (fields (field (name "POWER") "63mW") (field (name "TOLERANCE") "1%"))
      (libsource (lib "Turja Barua") (part "84D5KR2F"))
    )
    (comp (ref "R19")
      (value "4.7k")
      (footprint "RESC0402(1005)_L")
      (description "84K5 0.063W 1% 0402 (1005 Metric)  SMD")
      (fields (field (name "POWER") "63mW") (field (name "TOLERANCE") "1%"))
      (libsource (lib "Turja Barua") (part "84D5KR2F"))
    )
    (comp (ref "R20")
      (value "4.7k")
      (footprint "RESC0402(1005)_L")
      (description "84K5 0.063W 1% 0402 (1005 Metric)  SMD")
      (fields (field (name "POWER") "63mW") (field (name "TOLERANCE") "1%"))
      (libsource (lib "Turja Barua") (part "84D5KR2F"))
    )
    (comp (ref "R21")
      (value "4.7k")
      (footprint "RESC0402(1005)_L")
      (description "84K5 0.063W 1% 0402 (1005 Metric)  SMD")
      (fields (field (name "POWER") "63mW") (field (name "TOLERANCE") "1%"))
      (libsource (lib "Turja Barua") (part "84D5KR2F"))
    )
    (comp (ref "R22")
      (value "4.7k")
      (footprint "RESC0402(1005)_L")
      (description "84K5 0.063W 1% 0402 (1005 Metric)  SMD")
      (fields (field (name "POWER") "63mW") (field (name "TOLERANCE") "1%"))
      (libsource (lib "Turja Barua") (part "84D5KR2F"))
    )
    (comp (ref "R23")
      (value "4.7k")
      (footprint "RESC0402(1005)_L")
      (description "84K5 0.063W 1% 0402 (1005 Metric)  SMD")
      (fields (field (name "POWER") "63mW") (field (name "TOLERANCE") "1%"))
      (libsource (lib "Turja Barua") (part "84D5KR2F"))
    )
    (comp (ref "R24")
      (value "4.7k")
      (footprint "RESC0402(1005)_L")
      (description "84K5 0.063W 1% 0402 (1005 Metric)  SMD")
      (fields (field (name "POWER") "63mW") (field (name "TOLERANCE") "1%"))
      (libsource (lib "Turja Barua") (part "84D5KR2F"))
    )
    (comp (ref "R25")
      (value "24.9k")
      (footprint "RESC0402(1005)_L")
      (description "84K5 0.063W 1% 0402 (1005 Metric)  SMD")
      (fields (field (name "POWER") "63mW") (field (name "TOLERANCE") "1%"))
      (libsource (lib "Turja Barua") (part "84D5KR2F"))
    )
    (comp (ref "R26")
      (value "100k")
      (footprint "RESC0402(1005)_L")
      (description "84K5 0.063W 1% 0402 (1005 Metric)  SMD")
      (fields (field (name "POWER") "63mW") (field (name "TOLERANCE") "1%"))
      (libsource (lib "Turja Barua") (part "84D5KR2F"))
    )
    (comp (ref "R27")
      (value "100k")
      (footprint "RESC0402(1005)_L")
      (description "84K5 0.063W 1% 0402 (1005 Metric)  SMD")
      (fields (field (name "POWER") "63mW") (field (name "TOLERANCE") "1%"))
      (libsource (lib "Turja Barua") (part "84D5KR2F"))
    )
    (comp (ref "R28")
      (value "125k")
      (footprint "RESC0402(1005)_L")
      (description "84K5 0.063W 1% 0402 (1005 Metric)  SMD")
      (fields (field (name "POWER") "63mW") (field (name "TOLERANCE") "1%"))
      (libsource (lib "Turja Barua") (part "84D5KR2F"))
    )
    (comp (ref "R29")
      (value "100k")
      (footprint "RESC0402(1005)_L")
      (description "84K5 0.063W 1% 0402 (1005 Metric)  SMD")
      (fields (field (name "POWER") "63mW") (field (name "TOLERANCE") "1%"))
      (libsource (lib "Turja Barua") (part "84D5KR2F"))
    )
    (comp (ref "R30")
      (value "100k")
      (footprint "RESC0402(1005)_L")
      (description "84K5 0.063W 1% 0402 (1005 Metric)  SMD")
      (fields (field (name "POWER") "63mW") (field (name "TOLERANCE") "1%"))
      (libsource (lib "Turja Barua") (part "84D5KR2F"))
    )
    (comp (ref "R31")
      (value "100k")
      (footprint "RESC0402(1005)_L")
      (description "84K5 0.063W 1% 0402 (1005 Metric)  SMD")
      (fields (field (name "POWER") "63mW") (field (name "TOLERANCE") "1%"))
      (libsource (lib "Turja Barua") (part "84D5KR2F"))
    )
    (comp (ref "R32")
      (value "312k")
      (footprint "RESC0402(1005)_L")
      (description "84K5 0.063W 1% 0402 (1005 Metric)  SMD")
      (fields (field (name "POWER") "63mW") (field (name "TOLERANCE") "1%"))
      (libsource (lib "Turja Barua") (part "84D5KR2F"))
    )
    (comp (ref "R33")
      (value "100k")
      (footprint "RESC0402(1005)_L")
      (description "84K5 0.063W 1% 0402 (1005 Metric)  SMD")
      (fields (field (name "POWER") "63mW") (field (name "TOLERANCE") "1%"))
      (libsource (lib "Turja Barua") (part "84D5KR2F"))
    )
    (comp (ref "SW1")
      (value "25536NA6")
      (footprint "FP-25536NA6-0")
      (description "SWITCH SLIDE SPDT 4A 125V")
      (libsource (lib "Altium Content Vault") (part "52c419afdc2a387c7d548259a9aeefb"))
    )
    (comp (ref "U1")
      (value "XC7A100T-1CSG324C")
      (footprint "CSG324_XIL")
      (description "IC FPGA ARTIX7 210 I/O 324CSBGA")
      (fields (field (name "MOUSER PART NUMBER") "217-C7A100T-1CSG324C"))
      (libsource (lib "XC7A100T-1CSG324C") (part "XC7A100T-1CSG324C"))
    )
    (comp (ref "U2")
      (value "MT25QL128ABA1ESE-0SIT")
      (footprint "MICT-SE-8_L")
      (fields (field (name "MANUFACTURER") "Micron"))
      (libsource (lib "Altium Content Vault") (part "MICT-MT25QL128ABA-SOP2-8"))
    )
    (comp (ref "U3")
      (value "TPS62130ARGTR")
      (footprint "FP-RGT0016C-IPC_C")
      (description "3-V to 17-V, 3-A step-down converter with DCS-control in 3x3 QFN package 16-VQFN -40 to 125")
      (libsource (lib "Turja Barua") (part "dca50ec3578d8d47edbd046ea96d7ac"))
    )
    (comp (ref "U4")
      (value "TPS62130ARGTR")
      (footprint "FP-RGT0016C-IPC_C")
      (description "3-V to 17-V, 3-A step-down converter with DCS-control in 3x3 QFN package 16-VQFN -40 to 125")
      (libsource (lib "Turja Barua") (part "dca50ec3578d8d47edbd046ea96d7ac"))
    )
    (comp (ref "U5")
      (value "TPS62130ARGTR")
      (footprint "FP-RGT0016C-IPC_C")
      (description "3-V to 17-V, 3-A step-down converter with DCS-control in 3x3 QFN package 16-VQFN -40 to 125")
      (libsource (lib "Turja Barua") (part "dca50ec3578d8d47edbd046ea96d7ac"))
    )
    (comp (ref "X1")
      (value "DSC1001DL5-100.0000T")
      (footprint "FP-CDFN2520-4LD-PL-1-MFG")
      (libsource (lib "Altium Content Vault") (part "679220c3c234322ca52724a1007024e"))
    )
  )
  (nets
    (net (code "1") (name "/CLK100MHZ") (class "Default")
      (node (ref "U1") (pin "P17") (pinfunction "IO_L12P_T1_MRCC_14_P17") (pintype "passive"))
      (node (ref "X1") (pin "3") (pinfunction "Output_3") (pintype "passive"))
    )
    (net (code "2") (name "/HSYNC") (class "Default")
      (node (ref "R13") (pin "1") (pinfunction "1_1") (pintype "passive"))
      (node (ref "U1") (pin "H16") (pinfunction "IO_L13P_T2_MRCC_15_H16") (pintype "passive"))
    )
    (net (code "3") (name "/QSPI_CCLK") (class "Default")
      (node (ref "U1") (pin "E9") (pinfunction "CCLK_0_E9") (pintype "passive"))
      (node (ref "U2") (pin "6") (pinfunction "C_6") (pintype "input"))
    )
    (net (code "4") (name "/QSPI_CS_B") (class "Default")
      (node (ref "R16") (pin "1") (pinfunction "1_1") (pintype "passive"))
      (node (ref "U1") (pin "L13") (pinfunction "IO_L6P_T0_FCS_B_14_L13") (pintype "passive"))
      (node (ref "U2") (pin "1") (pinfunction "S#_1") (pintype "input"))
    )
    (net (code "5") (name "/QSPI_DQ0") (class "Default")
      (node (ref "U1") (pin "K17") (pinfunction "IO_L1P_T0_D00_MOSI_14_K17") (pintype "passive"))
      (node (ref "U2") (pin "5") (pinfunction "DQ0_5") (pintype "bidirectional"))
    )
    (net (code "6") (name "/QSPI_DQ1") (class "Default")
      (node (ref "U1") (pin "K18") (pinfunction "IO_L1N_T0_D01_DIN_14_K18") (pintype "passive"))
      (node (ref "U2") (pin "2") (pinfunction "DQ1_2") (pintype "bidirectional"))
    )
    (net (code "7") (name "/QSPI_DQ2") (class "Default")
      (node (ref "R17") (pin "2") (pinfunction "2_2") (pintype "passive"))
      (node (ref "U1") (pin "L14") (pinfunction "IO_L2P_T0_D02_14_L14") (pintype "passive"))
      (node (ref "U2") (pin "3") (pinfunction "W#/DQ2_3") (pintype "bidirectional"))
    )
    (net (code "8") (name "/QSPI_DQ3") (class "Default")
      (node (ref "R18") (pin "2") (pinfunction "2_2") (pintype "passive"))
      (node (ref "U1") (pin "M14") (pinfunction "IO_L2N_T0_D03_14_M14") (pintype "passive"))
      (node (ref "U2") (pin "7") (pinfunction "HOLD#/DQ3_7") (pintype "bidirectional"))
    )
    (net (code "9") (name "/SW0") (class "Default")
      (node (ref "SW1") (pin "2") (pinfunction "2_2") (pintype "passive"))
      (node (ref "U1") (pin "F15") (pinfunction "IO_L14P_T2_SRCC_15_F15") (pintype "passive"))
    )
    (net (code "10") (name "/TCK") (class "Default")
      (node (ref "J2") (pin "3") (pinfunction "3_3") (pintype "passive"))
      (node (ref "U1") (pin "E10") (pinfunction "TCK_0_E10") (pintype "passive"))
    )
    (net (code "11") (name "/TDI") (class "Default")
      (node (ref "J2") (pin "7") (pinfunction "7_7") (pintype "passive"))
      (node (ref "U1") (pin "E11") (pinfunction "TDI_0_E11") (pintype "passive"))
    )
    (net (code "12") (name "/TDO") (class "Default")
      (node (ref "J2") (pin "5") (pinfunction "5_5") (pintype "passive"))
      (node (ref "U1") (pin "E13") (pinfunction "TDO_0_E13") (pintype "passive"))
    )
    (net (code "13") (name "/TMS") (class "Default")
      (node (ref "J2") (pin "9") (pinfunction "9_9") (pintype "passive"))
      (node (ref "U1") (pin "E12") (pinfunction "TMS_0_E12") (pintype "passive"))
    )
    (net (code "14") (name "/VCCAUX_1V8") (class "Default")
      (node (ref "C15") (pin "2") (pinfunction "2_2") (pintype "passive"))
      (node (ref "C16") (pin "1") (pinfunction "1_1") (pintype "passive"))
      (node (ref "C17") (pin "1") (pinfunction "1_1") (pintype "passive"))
      (node (ref "C50") (pin "2") (pinfunction "2_2") (pintype "passive"))
      (node (ref "C51") (pin "2") (pinfunction "2_2") (pintype "passive"))
      (node (ref "C66") (pin "2") (pinfunction "2_2") (pintype "passive"))
      (node (ref "L2") (pin "2") (pinfunction "2_2") (pintype "passive"))
      (node (ref "R28") (pin "1") (pinfunction "1_1") (pintype "passive"))
      (node (ref "R30") (pin "2") (pinfunction "2_2") (pintype "passive"))
      (node (ref "U1") (pin "F12") (pinfunction "VCCAUX_1_F12") (pintype "passive"))
      (node (ref "U1") (pin "H10") (pinfunction "VCCADC_0_H10") (pintype "passive"))
      (node (ref "U1") (pin "H12") (pinfunction "VCCAUX_2_H12") (pintype "passive"))
      (node (ref "U1") (pin "K12") (pinfunction "VCCAUX_3_K12") (pintype "passive"))
      (node (ref "U1") (pin "M12") (pinfunction "VCCAUX_4_M12") (pintype "passive"))
      (node (ref "U4") (pin "14") (pinfunction "VOS_14") (pintype "input"))
    )
    (net (code "15") (name "/VCCAUX_FB") (class "Default")
      (node (ref "R28") (pin "2") (pinfunction "2_2") (pintype "passive"))
      (node (ref "R29") (pin "1") (pinfunction "1_1") (pintype "passive"))
      (node (ref "U4") (pin "5") (pinfunction "FB_5") (pintype "input"))
    )
    (net (code "16") (name "/VCCAUX_PG") (class "Default")
      (node (ref "R30") (pin "1") (pinfunction "1_1") (pintype "passive"))
      (node (ref "U4") (pin "4") (pinfunction "PG_4") (pintype "output"))
    )
    (net (code "17") (name "/VCCAUX_SS") (class "Default")
      (node (ref "C52") (pin "2") (pinfunction "2_2") (pintype "passive"))
      (node (ref "U4") (pin "9") (pinfunction "SS/TR_9") (pintype "input"))
    )
    (net (code "18") (name "/VCCAUX_SW") (class "Default")
      (node (ref "L2") (pin "1") (pinfunction "1_1") (pintype "passive"))
      (node (ref "U4") (pin "1") (pinfunction "SW_1") (pintype "output"))
      (node (ref "U4") (pin "2") (pinfunction "SW_2") (pintype "output"))
      (node (ref "U4") (pin "3") (pinfunction "SW_3") (pintype "output"))
    )
    (net (code "19") (name "/VCCINT_1V0") (class "Default")
      (node (ref "C10") (pin "2") (pinfunction "2_2") (pintype "passive"))
      (node (ref "C11") (pin "2") (pinfunction "2_2") (pintype "passive"))
      (node (ref "C12") (pin "2") (pinfunction "2_2") (pintype "passive"))
      (node (ref "C13") (pin "2") (pinfunction "2_2") (pintype "passive"))
      (node (ref "C14") (pin "2") (pinfunction "2_2") (pintype "passive"))
      (node (ref "C2") (pin "1") (pinfunction "1_1") (pintype "passive"))
      (node (ref "C3") (pin "1") (pinfunction "1_1") (pintype "passive"))
      (node (ref "C4") (pin "1") (pinfunction "1_1") (pintype "passive"))
      (node (ref "C45") (pin "2") (pinfunction "2_2") (pintype "passive"))
      (node (ref "C46") (pin "2") (pinfunction "2_2") (pintype "passive"))
      (node (ref "C5") (pin "1") (pinfunction "1_1") (pintype "passive"))
      (node (ref "C6") (pin "2") (pinfunction "2_2") (pintype "passive"))
      (node (ref "C60") (pin "2") (pinfunction "2_2") (pintype "passive"))
      (node (ref "C63") (pin "2") (pinfunction "2_2") (pintype "passive"))
      (node (ref "C7") (pin "1") (pinfunction "1_1") (pintype "passive"))
      (node (ref "C8") (pin "1") (pinfunction "1_1") (pintype "passive"))
      (node (ref "C9") (pin "1") (pinfunction "1_1") (pintype "passive"))
      (node (ref "L1") (pin "2") (pinfunction "2_2") (pintype "passive"))
      (node (ref "R25") (pin "1") (pinfunction "1_1") (pintype "passive"))
      (node (ref "R27") (pin "2") (pinfunction "2_2") (pintype "passive"))
      (node (ref "U1") (pin "F10") (pinfunction "VCCBRAM_1_F10") (pintype "passive"))
      (node (ref "U1") (pin "F8") (pinfunction "VCCINT_1_F8") (pintype "passive"))
      (node (ref "U1") (pin "G11") (pinfunction "VCCBRAM_2_G11") (pintype "passive"))
      (node (ref "U1") (pin "G7") (pinfunction "VCCINT_2_G7") (pintype "passive"))
      (node (ref "U1") (pin "G9") (pinfunction "VCCINT_3_G9") (pintype "passive"))
      (node (ref "U1") (pin "H8") (pinfunction "VCCINT_4_H8") (pintype "passive"))
      (node (ref "U1") (pin "J11") (pinfunction "VCCINT_6_J11") (pintype "passive"))
      (node (ref "U1") (pin "J7") (pinfunction "VCCINT_5_J7") (pintype "passive"))
      (node (ref "U1") (pin "K8") (pinfunction "VCCINT_7_K8") (pintype "passive"))
      (node (ref "U1") (pin "L11") (pinfunction "VCCINT_9_L11") (pintype "passive"))
      (node (ref "U1") (pin "L7") (pinfunction "VCCINT_8_L7") (pintype "passive"))
      (node (ref "U1") (pin "M10") (pinfunction "VCCINT_11_M10") (pintype "passive"))
      (node (ref "U1") (pin "M8") (pinfunction "VCCINT_10_M8") (pintype "passive"))
      (node (ref "U1") (pin "N11") (pinfunction "VCCINT_14_N11") (pintype "passive"))
      (node (ref "U1") (pin "N7") (pinfunction "VCCINT_12_N7") (pintype "passive"))
      (node (ref "U1") (pin "N9") (pinfunction "VCCINT_13_N9") (pintype "passive"))
      (node (ref "U3") (pin "14") (pinfunction "VOS_14") (pintype "input"))
    )
    (net (code "20") (name "/VCCINT_FB") (class "Default")
      (node (ref "R25") (pin "2") (pinfunction "2_2") (pintype "passive"))
      (node (ref "R26") (pin "1") (pinfunction "1_1") (pintype "passive"))
      (node (ref "U3") (pin "5") (pinfunction "FB_5") (pintype "input"))
    )
    (net (code "21") (name "/VCCINT_PG") (class "Default")
      (node (ref "R27") (pin "1") (pinfunction "1_1") (pintype "passive"))
      (node (ref "U3") (pin "4") (pinfunction "PG_4") (pintype "output"))
    )
    (net (code "22") (name "/VCCINT_SS") (class "Default")
      (node (ref "C47") (pin "2") (pinfunction "2_2") (pintype "passive"))
      (node (ref "U3") (pin "9") (pinfunction "SS/TR_9") (pintype "input"))
    )
    (net (code "23") (name "/VCCINT_SW") (class "Default")
      (node (ref "L1") (pin "1") (pinfunction "1_1") (pintype "passive"))
      (node (ref "U3") (pin "1") (pinfunction "SW_1") (pintype "output"))
      (node (ref "U3") (pin "2") (pinfunction "SW_2") (pintype "output"))
      (node (ref "U3") (pin "3") (pinfunction "SW_3") (pintype "output"))
    )
    (net (code "24") (name "/VCCO_3V3") (class "Default")
      (node (ref "C1") (pin "1") (pinfunction "1_1") (pintype "passive"))
      (node (ref "C18") (pin "2") (pinfunction "2_2") (pintype "passive"))
      (node (ref "C19") (pin "2") (pinfunction "2_2") (pintype "passive"))
      (node (ref "C20") (pin "2") (pinfunction "2_2") (pintype "passive"))
      (node (ref "C21") (pin "2") (pinfunction "2_2") (pintype "passive"))
      (node (ref "C22") (pin "2") (pinfunction "2_2") (pintype "passive"))
      (node (ref "C23") (pin "2") (pinfunction "2_2") (pintype "passive"))
      (node (ref "C24") (pin "2") (pinfunction "2_2") (pintype "passive"))
      (node (ref "C25") (pin "2") (pinfunction "2_2") (pintype "passive"))
      (node (ref "C26") (pin "2") (pinfunction "2_2") (pintype "passive"))
      (node (ref "C27") (pin "2") (pinfunction "2_2") (pintype "passive"))
      (node (ref "C28") (pin "2") (pinfunction "2_2") (pintype "passive"))
      (node (ref "C29") (pin "1") (pinfunction "1_1") (pintype "passive"))
      (node (ref "C30") (pin "2") (pinfunction "2_2") (pintype "passive"))
      (node (ref "C31") (pin "1") (pinfunction "1_1") (pintype "passive"))
      (node (ref "C32") (pin "1") (pinfunction "1_1") (pintype "passive"))
      (node (ref "C33") (pin "1") (pinfunction "1_1") (pintype "passive"))
      (node (ref "C34") (pin "1") (pinfunction "1_1") (pintype "passive"))
      (node (ref "C35") (pin "1") (pinfunction "1_1") (pintype "passive"))
      (node (ref "C36") (pin "1") (pinfunction "1_1") (pintype "passive"))
      (node (ref "C37") (pin "1") (pinfunction "1_1") (pintype "passive"))
      (node (ref "C38") (pin "1") (pinfunction "1_1") (pintype "passive"))
      (node (ref "C39") (pin "1") (pinfunction "1_1") (pintype "passive"))
      (node (ref "C40") (pin "1") (pinfunction "1_1") (pintype "passive"))
      (node (ref "C41") (pin "1") (pinfunction "1_1") (pintype "passive"))
      (node (ref "C42") (pin "1") (pinfunction "1_1") (pintype "passive"))
      (node (ref "C53") (pin "2") (pinfunction "2_2") (pintype "passive"))
      (node (ref "C57") (pin "2") (pinfunction "2_2") (pintype "passive"))
      (node (ref "C59") (pin "1") (pinfunction "1_1") (pintype "passive"))
      (node (ref "C61") (pin "1") (pinfunction "1_1") (pintype "passive"))
      (node (ref "J2") (pin "1") (pinfunction "1_1") (pintype "passive"))
      (node (ref "L3") (pin "2") (pinfunction "2_2") (pintype "passive"))
      (node (ref "R16") (pin "2") (pinfunction "2_2") (pintype "passive"))
      (node (ref "R17") (pin "1") (pinfunction "1_1") (pintype "passive"))
      (node (ref "R18") (pin "1") (pinfunction "1_1") (pintype "passive"))
      (node (ref "R19") (pin "2") (pinfunction "2_2") (pintype "passive"))
      (node (ref "R22") (pin "2") (pinfunction "2_2") (pintype "passive"))
      (node (ref "R23") (pin "2") (pinfunction "2_2") (pintype "passive"))
      (node (ref "R24") (pin "2") (pinfunction "2_2") (pintype "passive"))
      (node (ref "R32") (pin "1") (pinfunction "1_1") (pintype "passive"))
      (node (ref "R33") (pin "2") (pinfunction "2_2") (pintype "passive"))
      (node (ref "SW1") (pin "1") (pinfunction "1_1") (pintype "passive"))
      (node (ref "U1") (pin "A17") (pinfunction "VCCO_15_1_A17") (pintype "passive"))
      (node (ref "U1") (pin "A7") (pinfunction "VCCO_35_1_A7") (pintype "passive"))
      (node (ref "U1") (pin "B10") (pinfunction "VCCO_16_B10") (pintype "passive"))
      (node (ref "U1") (pin "C13") (pinfunction "VCCO_15_2_C13") (pintype "passive"))
      (node (ref "U1") (pin "C3") (pinfunction "VCCO_35_2_C3") (pintype "passive"))
      (node (ref "U1") (pin "D16") (pinfunction "VCCO_15_3_D16") (pintype "passive"))
      (node (ref "U1") (pin "D6") (pinfunction "VCCO_35_3_D6") (pintype "passive"))
      (node (ref "U1") (pin "F2") (pinfunction "VCCO_35_4_F2") (pintype "passive"))
      (node (ref "U1") (pin "G15") (pinfunction "VCCO_15_4_G15") (pintype "passive"))
      (node (ref "U1") (pin "G5") (pinfunction "VCCO_35_5_G5") (pintype "passive"))
      (node (ref "U1") (pin "H18") (pinfunction "VCCO_15_5_H18") (pintype "passive"))
      (node (ref "U1") (pin "J1") (pinfunction "VCCO_35_6_J1") (pintype "passive"))
      (node (ref "U1") (pin "K14") (pinfunction "VCCO_15_6_K14") (pintype "passive"))
      (node (ref "U1") (pin "K4") (pinfunction "VCCO_34_1_K4") (pintype "passive"))
      (node (ref "U1") (pin "L17") (pinfunction "VCCO_14_1_L17") (pintype "passive"))
      (node (ref "U1") (pin "N13") (pinfunction "VCCO_14_2_N13") (pintype "passive"))
      (node (ref "U1") (pin "N3") (pinfunction "VCCO_34_2_N3") (pintype "passive"))
      (node (ref "U1") (pin "P16") (pinfunction "VCCO_14_3_P16") (pintype "passive"))
      (node (ref "U1") (pin "P6") (pinfunction "VCCO_34_3_P6") (pintype "passive"))
      (node (ref "U1") (pin "P8") (pinfunction "CFGBVS_0_P8") (pintype "passive"))
      (node (ref "U1") (pin "R9") (pinfunction "VCCO_0_R9") (pintype "passive"))
      (node (ref "U1") (pin "T12") (pinfunction "VCCO_14_4_T12") (pintype "passive"))
      (node (ref "U1") (pin "T2") (pinfunction "VCCO_34_4_T2") (pintype "passive"))
      (node (ref "U1") (pin "U15") (pinfunction "VCCO_14_5_U15") (pintype "passive"))
      (node (ref "U1") (pin "U5") (pinfunction "VCCO_34_5_U5") (pintype "passive"))
      (node (ref "U1") (pin "V18") (pinfunction "VCCO_14_6_V18") (pintype "passive"))
      (node (ref "U1") (pin "V8") (pinfunction "VCCO_34_6_V8") (pintype "passive"))
      (node (ref "U2") (pin "8") (pinfunction "VCC_8") (pintype "power_in"))
      (node (ref "U5") (pin "14") (pinfunction "VOS_14") (pintype "input"))
      (node (ref "X1") (pin "1") (pinfunction "~{Standby}_1") (pintype "input"))
      (node (ref "X1") (pin "4") (pinfunction "VDD_4") (pintype "power_in"))
    )
    (net (code "25") (name "/VCCO_FB") (class "Default")
      (node (ref "R31") (pin "1") (pinfunction "1_1") (pintype "passive"))
      (node (ref "R32") (pin "2") (pinfunction "2_2") (pintype "passive"))
      (node (ref "U5") (pin "5") (pinfunction "FB_5") (pintype "input"))
    )
    (net (code "26") (name "/VCCO_PG") (class "Default")
      (node (ref "R33") (pin "1") (pinfunction "1_1") (pintype "passive"))
      (node (ref "U5") (pin "4") (pinfunction "PG_4") (pintype "output"))
    )
    (net (code "27") (name "/VCCO_SS") (class "Default")
      (node (ref "C56") (pin "2") (pinfunction "2_2") (pintype "passive"))
      (node (ref "U5") (pin "9") (pinfunction "SS/TR_9") (pintype "input"))
    )
    (net (code "28") (name "/VCCO_SW") (class "Default")
      (node (ref "L3") (pin "1") (pinfunction "1_1") (pintype "passive"))
      (node (ref "U5") (pin "1") (pinfunction "SW_1") (pintype "output"))
      (node (ref "U5") (pin "2") (pinfunction "SW_2") (pintype "output"))
      (node (ref "U5") (pin "3") (pinfunction "SW_3") (pintype "output"))
    )
    (net (code "29") (name "/VGA_B0") (class "Default")
      (node (ref "R9") (pin "1") (pinfunction "1_1") (pintype "passive"))
      (node (ref "U1") (pin "E15") (pinfunction "IO_L11P_T1_SRCC_15_E15") (pintype "passive"))
    )
    (net (code "30") (name "/VGA_B1") (class "Default")
      (node (ref "R10") (pin "1") (pinfunction "1_1") (pintype "passive"))
      (node (ref "U1") (pin "C15") (pinfunction "IO_L12N_T1_MRCC_15_C15") (pintype "passive"))
    )
    (net (code "31") (name "/VGA_B2") (class "Default")
      (node (ref "R11") (pin "1") (pinfunction "1_1") (pintype "passive"))
      (node (ref "U1") (pin "D15") (pinfunction "IO_L12P_T1_MRCC_15_D15") (pintype "passive"))
    )
    (net (code "32") (name "/VGA_B3") (class "Default")
      (node (ref "R12") (pin "1") (pinfunction "1_1") (pintype "passive"))
      (node (ref "U1") (pin "G16") (pinfunction "IO_L13N_T2_MRCC_15_G16") (pintype "passive"))
    )
    (net (code "33") (name "/VGA_B_ANALOG") (class "Default")
      (node (ref "J1") (pin "3") (pinfunction "3_3") (pintype "passive"))
      (node (ref "R10") (pin "2") (pinfunction "2_2") (pintype "passive"))
      (node (ref "R11") (pin "2") (pinfunction "2_2") (pintype "passive"))
      (node (ref "R12") (pin "2") (pinfunction "2_2") (pintype "passive"))
      (node (ref "R9") (pin "2") (pinfunction "2_2") (pintype "passive"))
    )
    (net (code "34") (name "/VGA_G0") (class "Default")
      (node (ref "R5") (pin "1") (pinfunction "1_1") (pintype "passive"))
      (node (ref "U1") (pin "E18") (pinfunction "IO_L21P_T3_DQS_15_E18") (pintype "passive"))
    )
    (net (code "35") (name "/VGA_G1") (class "Default")
      (node (ref "R6") (pin "1") (pinfunction "1_1") (pintype "passive"))
      (node (ref "U1") (pin "G13") (pinfunction "IO_0_15_G13") (pintype "passive"))
    )
    (net (code "36") (name "/VGA_G2") (class "Default")
      (node (ref "R7") (pin "1") (pinfunction "1_1") (pintype "passive"))
      (node (ref "U1") (pin "K16") (pinfunction "IO_25_15_K16") (pintype "passive"))
    )
    (net (code "37") (name "/VGA_G3") (class "Default")
      (node (ref "R8") (pin "1") (pinfunction "1_1") (pintype "passive"))
      (node (ref "U1") (pin "E16") (pinfunction "IO_L11N_T1_SRCC_15_E16") (pintype "passive"))
    )
    (net (code "38") (name "/VGA_G_ANALOG") (class "Default")
      (node (ref "J1") (pin "2") (pinfunction "2_2") (pintype "passive"))
      (node (ref "R5") (pin "2") (pinfunction "2_2") (pintype "passive"))
      (node (ref "R6") (pin "2") (pinfunction "2_2") (pintype "passive"))
      (node (ref "R7") (pin "2") (pinfunction "2_2") (pintype "passive"))
      (node (ref "R8") (pin "2") (pinfunction "2_2") (pintype "passive"))
    )
    (net (code "39") (name "/VGA_HSYNC") (class "Default")
      (node (ref "J1") (pin "13") (pinfunction "13_13") (pintype "passive"))
      (node (ref "R13") (pin "2") (pinfunction "2_2") (pintype "passive"))
    )
    (net (code "40") (name "/VGA_R0") (class "Default")
      (node (ref "R1") (pin "1") (pinfunction "1_1") (pintype "passive"))
      (node (ref "U1") (pin "A11") (pinfunction "IO_L4N_T0_15_A11") (pintype "passive"))
    )
    (net (code "41") (name "/VGA_R1") (class "Default")
      (node (ref "R2") (pin "1") (pinfunction "1_1") (pintype "passive"))
      (node (ref "U1") (pin "B11") (pinfunction "IO_L4P_T0_15_B11") (pintype "passive"))
    )
    (net (code "42") (name "/VGA_R2") (class "Default")
      (node (ref "R3") (pin "1") (pinfunction "1_1") (pintype "passive"))
      (node (ref "U1") (pin "D12") (pinfunction "IO_L6P_T0_15_D12") (pintype "passive"))
    )
    (net (code "43") (name "/VGA_R3") (class "Default")
      (node (ref "R4") (pin "1") (pinfunction "1_1") (pintype "passive"))
      (node (ref "U1") (pin "H14") (pinfunction "IO_L15P_T2_DQS_15_H14") (pintype "passive"))
    )
    (net (code "44") (name "/VGA_R_ANALOG") (class "Default")
      (node (ref "J1") (pin "1") (pinfunction "1_1") (pintype "passive"))
      (node (ref "R1") (pin "2") (pinfunction "2_2") (pintype "passive"))
      (node (ref "R2") (pin "2") (pinfunction "2_2") (pintype "passive"))
      (node (ref "R3") (pin "2") (pinfunction "2_2") (pintype "passive"))
      (node (ref "R4") (pin "2") (pinfunction "2_2") (pintype "passive"))
    )
    (net (code "45") (name "/VGA_VSYNC") (class "Default")
      (node (ref "J1") (pin "14") (pinfunction "14_14") (pintype "passive"))
      (node (ref "R14") (pin "2") (pinfunction "2_2") (pintype "passive"))
    )
    (net (code "46") (name "/VIN") (class "Default")
      (node (ref "C44") (pin "2") (pinfunction "2_2") (pintype "passive"))
      (node (ref "C48") (pin "2") (pinfunction "2_2") (pintype "passive"))
      (node (ref "C49") (pin "2") (pinfunction "2_2") (pintype "passive"))
      (node (ref "C54") (pin "2") (pinfunction "2_2") (pintype "passive"))
      (node (ref "C55") (pin "2") (pinfunction "2_2") (pintype "passive"))
      (node (ref "C62") (pin "2") (pinfunction "2_2") (pintype "passive"))
      (node (ref "C64") (pin "1") (pinfunction "1_1") (pintype "passive"))
      (node (ref "C65") (pin "2") (pinfunction "2_2") (pintype "passive"))
      (node (ref "J3") (pin "1") (pinfunction "1_1") (pintype "passive"))
      (node (ref "U3") (pin "10") (pinfunction "AVIN_10") (pintype "input"))
      (node (ref "U3") (pin "11") (pinfunction "PVIN_11") (pintype "input"))
      (node (ref "U3") (pin "12") (pinfunction "PVIN_12") (pintype "input"))
      (node (ref "U3") (pin "13") (pinfunction "EN_13") (pintype "input"))
      (node (ref "U4") (pin "10") (pinfunction "AVIN_10") (pintype "input"))
      (node (ref "U4") (pin "11") (pinfunction "PVIN_11") (pintype "input"))
      (node (ref "U4") (pin "12") (pinfunction "PVIN_12") (pintype "input"))
      (node (ref "U4") (pin "13") (pinfunction "EN_13") (pintype "input"))
      (node (ref "U5") (pin "10") (pinfunction "AVIN_10") (pintype "input"))
      (node (ref "U5") (pin "11") (pinfunction "PVIN_11") (pintype "input"))
      (node (ref "U5") (pin "12") (pinfunction "PVIN_12") (pintype "input"))
      (node (ref "U5") (pin "13") (pinfunction "EN_13") (pintype "input"))
    )
    (net (code "47") (name "/VSYNC") (class "Default")
      (node (ref "R14") (pin "1") (pinfunction "1_1") (pintype "passive"))
      (node (ref "U1") (pin "F16") (pinfunction "IO_L14N_T2_SRCC_15_F16") (pintype "passive"))
    )
    (net (code "48") (name "GND") (class "Default")
      (node (ref "C1") (pin "2") (pinfunction "2_2") (pintype "passive"))
      (node (ref "C10") (pin "1") (pinfunction "1_1") (pintype "passive"))
      (node (ref "C11") (pin "1") (pinfunction "1_1") (pintype "passive"))
      (node (ref "C12") (pin "1") (pinfunction "1_1") (pintype "passive"))
      (node (ref "C13") (pin "1") (pinfunction "1_1") (pintype "passive"))
      (node (ref "C14") (pin "1") (pinfunction "1_1") (pintype "passive"))
      (node (ref "C15") (pin "1") (pinfunction "1_1") (pintype "passive"))
      (node (ref "C16") (pin "2") (pinfunction "2_2") (pintype "passive"))
      (node (ref "C17") (pin "2") (pinfunction "2_2") (pintype "passive"))
      (node (ref "C18") (pin "1") (pinfunction "1_1") (pintype "passive"))
      (node (ref "C19") (pin "1") (pinfunction "1_1") (pintype "passive"))
      (node (ref "C2") (pin "2") (pinfunction "2_2") (pintype "passive"))
      (node (ref "C20") (pin "1") (pinfunction "1_1") (pintype "passive"))
      (node (ref "C21") (pin "1") (pinfunction "1_1") (pintype "passive"))
      (node (ref "C22") (pin "1") (pinfunction "1_1") (pintype "passive"))
      (node (ref "C23") (pin "1") (pinfunction "1_1") (pintype "passive"))
      (node (ref "C24") (pin "1") (pinfunction "1_1") (pintype "passive"))
      (node (ref "C25") (pin "1") (pinfunction "1_1") (pintype "passive"))
      (node (ref "C26") (pin "1") (pinfunction "1_1") (pintype "passive"))
      (node (ref "C27") (pin "1") (pinfunction "1_1") (pintype "passive"))
      (node (ref "C28") (pin "1") (pinfunction "1_1") (pintype "passive"))
      (node (ref "C29") (pin "2") (pinfunction "2_2") (pintype "passive"))
      (node (ref "C3") (pin "2") (pinfunction "2_2") (pintype "passive"))
      (node (ref "C30") (pin "1") (pinfunction "1_1") (pintype "passive"))
      (node (ref "C31") (pin "2") (pinfunction "2_2") (pintype "passive"))
      (node (ref "C32") (pin "2") (pinfunction "2_2") (pintype "passive"))
      (node (ref "C33") (pin "2") (pinfunction "2_2") (pintype "passive"))
      (node (ref "C34") (pin "2") (pinfunction "2_2") (pintype "passive"))
      (node (ref "C35") (pin "2") (pinfunction "2_2") (pintype "passive"))
      (node (ref "C36") (pin "2") (pinfunction "2_2") (pintype "passive"))
      (node (ref "C37") (pin "2") (pinfunction "2_2") (pintype "passive"))
      (node (ref "C38") (pin "2") (pinfunction "2_2") (pintype "passive"))
      (node (ref "C39") (pin "2") (pinfunction "2_2") (pintype "passive"))
      (node (ref "C4") (pin "2") (pinfunction "2_2") (pintype "passive"))
      (node (ref "C40") (pin "2") (pinfunction "2_2") (pintype "passive"))
      (node (ref "C41") (pin "2") (pinfunction "2_2") (pintype "passive"))
      (node (ref "C42") (pin "2") (pinfunction "2_2") (pintype "passive"))
      (node (ref "C44") (pin "1") (pinfunction "1_1") (pintype "passive"))
      (node (ref "C45") (pin "1") (pinfunction "1_1") (pintype "passive"))
      (node (ref "C46") (pin "1") (pinfunction "1_1") (pintype "passive"))
      (node (ref "C47") (pin "1") (pinfunction "1_1") (pintype "passive"))
      (node (ref "C48") (pin "1") (pinfunction "1_1") (pintype "passive"))
      (node (ref "C49") (pin "1") (pinfunction "1_1") (pintype "passive"))
      (node (ref "C5") (pin "2") (pinfunction "2_2") (pintype "passive"))
      (node (ref "C50") (pin "1") (pinfunction "1_1") (pintype "passive"))
      (node (ref "C51") (pin "1") (pinfunction "1_1") (pintype "passive"))
      (node (ref "C52") (pin "1") (pinfunction "1_1") (pintype "passive"))
      (node (ref "C53") (pin "1") (pinfunction "1_1") (pintype "passive"))
      (node (ref "C54") (pin "1") (pinfunction "1_1") (pintype "passive"))
      (node (ref "C55") (pin "1") (pinfunction "1_1") (pintype "passive"))
      (node (ref "C56") (pin "1") (pinfunction "1_1") (pintype "passive"))
      (node (ref "C57") (pin "1") (pinfunction "1_1") (pintype "passive"))
      (node (ref "C59") (pin "2") (pinfunction "2_2") (pintype "passive"))
      (node (ref "C6") (pin "1") (pinfunction "1_1") (pintype "passive"))
      (node (ref "C60") (pin "1") (pinfunction "1_1") (pintype "passive"))
      (node (ref "C61") (pin "2") (pinfunction "2_2") (pintype "passive"))
      (node (ref "C62") (pin "1") (pinfunction "1_1") (pintype "passive"))
      (node (ref "C63") (pin "1") (pinfunction "1_1") (pintype "passive"))
      (node (ref "C64") (pin "2") (pinfunction "2_2") (pintype "passive"))
      (node (ref "C65") (pin "1") (pinfunction "1_1") (pintype "passive"))
      (node (ref "C66") (pin "1") (pinfunction "1_1") (pintype "passive"))
      (node (ref "C7") (pin "2") (pinfunction "2_2") (pintype "passive"))
      (node (ref "C8") (pin "2") (pinfunction "2_2") (pintype "passive"))
      (node (ref "C9") (pin "2") (pinfunction "2_2") (pintype "passive"))
      (node (ref "J1") (pin "10") (pinfunction "10_10") (pintype "passive"))
      (node (ref "J1") (pin "11") (pinfunction "11_11") (pintype "passive"))
      (node (ref "J1") (pin "12") (pinfunction "12_12") (pintype "passive"))
      (node (ref "J1") (pin "15") (pinfunction "15_15") (pintype "passive"))
      (node (ref "J1") (pin "4") (pinfunction "4_4") (pintype "passive"))
      (node (ref "J1") (pin "5") (pinfunction "5_5") (pintype "passive"))
      (node (ref "J1") (pin "6") (pinfunction "6_6") (pintype "passive"))
      (node (ref "J1") (pin "7") (pinfunction "7_7") (pintype "passive"))
      (node (ref "J1") (pin "8") (pinfunction "8_8") (pintype "passive"))
      (node (ref "J1") (pin "9") (pinfunction "9_9") (pintype "passive"))
      (node (ref "J1") (pin "M1") (pinfunction "M1_M1") (pintype "passive"))
      (node (ref "J1") (pin "M2") (pinfunction "M2_M2") (pintype "passive"))
      (node (ref "J2") (pin "10") (pinfunction "10_10") (pintype "passive"))
      (node (ref "J2") (pin "2") (pinfunction "2_2") (pintype "passive"))
      (node (ref "J2") (pin "4") (pinfunction "4_4") (pintype "passive"))
      (node (ref "J2") (pin "6") (pinfunction "6_6") (pintype "passive"))
      (node (ref "J2") (pin "8") (pinfunction "8_8") (pintype "passive"))
      (node (ref "J3") (pin "2") (pinfunction "2_2") (pintype "passive"))
      (node (ref "R20") (pin "2") (pinfunction "2_2") (pintype "passive"))
      (node (ref "R21") (pin "2") (pinfunction "2_2") (pintype "passive"))
      (node (ref "R26") (pin "2") (pinfunction "2_2") (pintype "passive"))
      (node (ref "R29") (pin "2") (pinfunction "2_2") (pintype "passive"))
      (node (ref "R31") (pin "2") (pinfunction "2_2") (pintype "passive"))
      (node (ref "SW1") (pin "3") (pinfunction "3_3") (pintype "passive"))
      (node (ref "U1") (pin "A12") (pinfunction "GND_2_A12") (pintype "passive"))
      (node (ref "U1") (pin "A2") (pinfunction "GND_1_A2") (pintype "passive"))
      (node (ref "U1") (pin "B15") (pinfunction "GND_4_B15") (pintype "passive"))
      (node (ref "U1") (pin "B5") (pinfunction "GND_3_B5") (pintype "passive"))
      (node (ref "U1") (pin "C18") (pinfunction "GND_6_C18") (pintype "passive"))
      (node (ref "U1") (pin "C8") (pinfunction "GND_5_C8") (pintype "passive"))
      (node (ref "U1") (pin "D1") (pinfunction "GND_7_D1") (pintype "passive"))
      (node (ref "U1") (pin "D11") (pinfunction "GND_8_D11") (pintype "passive"))
      (node (ref "U1") (pin "E14") (pinfunction "GND_10_E14") (pintype "passive"))
      (node (ref "U1") (pin "E4") (pinfunction "GND_9_E4") (pintype "passive"))
      (node (ref "U1") (pin "E8") (pinfunction "VCCBATT_0_E8") (pintype "passive"))
      (node (ref "U1") (pin "F11") (pinfunction "GND_13_F11") (pintype "passive"))
      (node (ref "U1") (pin "F17") (pinfunction "GND_14_F17") (pintype "passive"))
      (node (ref "U1") (pin "F7") (pinfunction "GND_11_F7") (pintype "passive"))
      (node (ref "U1") (pin "F9") (pinfunction "GND_12_F9") (pintype "passive"))
      (node (ref "U1") (pin "G10") (pinfunction "GND_16_G10") (pintype "passive"))
      (node (ref "U1") (pin "G12") (pinfunction "GND_17_G12") (pintype "passive"))
      (node (ref "U1") (pin "G8") (pinfunction "GND_15_G8") (pintype "passive"))
      (node (ref "U1") (pin "H11") (pinfunction "GND_20_H11") (pintype "passive"))
      (node (ref "U1") (pin "H13") (pinfunction "GND_21_H13") (pintype "passive"))
      (node (ref "U1") (pin "H3") (pinfunction "GND_18_H3") (pintype "passive"))
      (node (ref "U1") (pin "H7") (pinfunction "GND_19_H7") (pintype "passive"))
      (node (ref "U1") (pin "H9") (pinfunction "GNDADC_0_H9") (pintype "passive"))
      (node (ref "U1") (pin "J10") (pinfunction "VP_0_J10") (pintype "passive"))
      (node (ref "U1") (pin "J12") (pinfunction "GND_24_J12") (pintype "passive"))
      (node (ref "U1") (pin "J16") (pinfunction "GND_25_J16") (pintype "passive"))
      (node (ref "U1") (pin "J6") (pinfunction "GND_22_J6") (pintype "passive"))
      (node (ref "U1") (pin "J8") (pinfunction "GND_23_J8") (pintype "passive"))
      (node (ref "U1") (pin "K11") (pinfunction "GND_27_K11") (pintype "passive"))
      (node (ref "U1") (pin "K7") (pinfunction "GND_26_K7") (pintype "passive"))
      (node (ref "U1") (pin "K9") (pinfunction "VN_0_K9") (pintype "passive"))
      (node (ref "U1") (pin "L12") (pinfunction "GND_30_L12") (pintype "passive"))
      (node (ref "U1") (pin "L2") (pinfunction "GND_28_L2") (pintype "passive"))
      (node (ref "U1") (pin "L8") (pinfunction "GND_29_L8") (pintype "passive"))
      (node (ref "U1") (pin "M11") (pinfunction "GND_34_M11") (pintype "passive"))
      (node (ref "U1") (pin "M15") (pinfunction "GND_35_M15") (pintype "passive"))
      (node (ref "U1") (pin "M5") (pinfunction "GND_31_M5") (pintype "passive"))
      (node (ref "U1") (pin "M7") (pinfunction "GND_32_M7") (pintype "passive"))
      (node (ref "U1") (pin "M9") (pinfunction "GND_33_M9") (pintype "passive"))
      (node (ref "U1") (pin "N10") (pinfunction "GND_37_N10") (pintype "passive"))
      (node (ref "U1") (pin "N12") (pinfunction "GND_38_N12") (pintype "passive"))
      (node (ref "U1") (pin "N18") (pinfunction "GND_39_N18") (pintype "passive"))
      (node (ref "U1") (pin "N8") (pinfunction "GND_36_N8") (pintype "passive"))
      (node (ref "U1") (pin "P1") (pinfunction "GND_40_P1") (pintype "passive"))
      (node (ref "U1") (pin "R14") (pinfunction "GND_42_R14") (pintype "passive"))
      (node (ref "U1") (pin "R4") (pinfunction "GND_41_R4") (pintype "passive"))
      (node (ref "U1") (pin "T17") (pinfunction "GND_44_T17") (pintype "passive"))
      (node (ref "U1") (pin "T7") (pinfunction "GND_43_T7") (pintype "passive"))
      (node (ref "U1") (pin "U10") (pinfunction "GND_45_U10") (pintype "passive"))
      (node (ref "U1") (pin "V13") (pinfunction "GND_47_V13") (pintype "passive"))
      (node (ref "U1") (pin "V3") (pinfunction "GND_46_V3") (pintype "passive"))
      (node (ref "U2") (pin "4") (pinfunction "VSS_4") (pintype "power_in"))
      (node (ref "U3") (pin "15") (pinfunction "PGND_15") (pintype "power_in"))
      (node (ref "U3") (pin "16") (pinfunction "PGND_16") (pintype "power_in"))
      (node (ref "U3") (pin "17") (pinfunction "Exposed_Thermal_Pad_17") (pintype "power_in"))
      (node (ref "U3") (pin "6") (pinfunction "AGND_6") (pintype "power_in"))
      (node (ref "U3") (pin "7") (pinfunction "FSW_7") (pintype "input"))
      (node (ref "U3") (pin "8") (pinfunction "DEF_8") (pintype "input"))
      (node (ref "U4") (pin "15") (pinfunction "PGND_15") (pintype "power_in"))
      (node (ref "U4") (pin "16") (pinfunction "PGND_16") (pintype "power_in"))
      (node (ref "U4") (pin "17") (pinfunction "Exposed_Thermal_Pad_17") (pintype "power_in"))
      (node (ref "U4") (pin "6") (pinfunction "AGND_6") (pintype "power_in"))
      (node (ref "U4") (pin "7") (pinfunction "FSW_7") (pintype "input"))
      (node (ref "U4") (pin "8") (pinfunction "DEF_8") (pintype "input"))
      (node (ref "U5") (pin "15") (pinfunction "PGND_15") (pintype "power_in"))
      (node (ref "U5") (pin "16") (pinfunction "PGND_16") (pintype "power_in"))
      (node (ref "U5") (pin "17") (pinfunction "Exposed_Thermal_Pad_17") (pintype "power_in"))
      (node (ref "U5") (pin "6") (pinfunction "AGND_6") (pintype "power_in"))
      (node (ref "U5") (pin "7") (pinfunction "FSW_7") (pintype "input"))
      (node (ref "U5") (pin "8") (pinfunction "DEF_8") (pintype "input"))
      (node (ref "X1") (pin "2") (pinfunction "GND_2") (pintype "power_in"))
    )
    (net (code "49") (name "Net-(U1-DONE_0)") (class "Default")
      (node (ref "R24") (pin "1") (pinfunction "1_1") (pintype "passive"))
      (node (ref "U1") (pin "P10") (pinfunction "DONE_0_P10") (pintype "passive"))
    )
    (net (code "50") (name "Net-(U1-INIT_B_0)") (class "Default")
      (node (ref "R23") (pin "1") (pinfunction "1_1") (pintype "passive"))
      (node (ref "U1") (pin "P7") (pinfunction "INIT_B_0_P7") (pintype "passive"))
    )
    (net (code "51") (name "Net-(U1-M0_0)") (class "Default")
      (node (ref "R19") (pin "1") (pinfunction "1_1") (pintype "passive"))
      (node (ref "U1") (pin "P12") (pinfunction "M0_0_P12") (pintype "passive"))
    )
    (net (code "52") (name "Net-(U1-M1_0)") (class "Default")
      (node (ref "R20") (pin "1") (pinfunction "1_1") (pintype "passive"))
      (node (ref "U1") (pin "P13") (pinfunction "M1_0_P13") (pintype "passive"))
    )
    (net (code "53") (name "Net-(U1-M2_0)") (class "Default")
      (node (ref "R21") (pin "1") (pinfunction "1_1") (pintype "passive"))
      (node (ref "U1") (pin "P11") (pinfunction "M2_0_P11") (pintype "passive"))
    )
    (net (code "54") (name "Net-(U1-PROGRAM_B_0)") (class "Default")
      (node (ref "R22") (pin "1") (pinfunction "1_1") (pintype "passive"))
      (node (ref "U1") (pin "P9") (pinfunction "PROGRAM_B_0_P9") (pintype "passive"))
    )
    (net (code "55") (name "unconnected-(U1-DXN_0-PadL9)") (class "Default")
      (node (ref "U1") (pin "L9") (pinfunction "DXN_0_L9") (pintype "passive"))
    )
    (net (code "56") (name "unconnected-(U1-DXP_0-PadL10)") (class "Default")
      (node (ref "U1") (pin "L10") (pinfunction "DXP_0_L10") (pintype "passive"))
    )
    (net (code "57") (name "unconnected-(U1-IO_0_14-PadR11)") (class "Default")
      (node (ref "U1") (pin "R11") (pinfunction "IO_0_14_R11") (pintype "passive"))
    )
    (net (code "58") (name "unconnected-(U1-IO_0_34-PadK6)") (class "Default")
      (node (ref "U1") (pin "K6") (pinfunction "IO_0_34_K6") (pintype "passive"))
    )
    (net (code "59") (name "unconnected-(U1-IO_0_35-PadF5)") (class "Default")
      (node (ref "U1") (pin "F5") (pinfunction "IO_0_35_F5") (pintype "passive"))
    )
    (net (code "60") (name "unconnected-(U1-IO_25_14-PadR10)") (class "Default")
      (node (ref "U1") (pin "R10") (pinfunction "IO_25_14_R10") (pintype "passive"))
    )
    (net (code "61") (name "unconnected-(U1-IO_25_34-PadU8)") (class "Default")
      (node (ref "U1") (pin "U8") (pinfunction "IO_25_34_U8") (pintype "passive"))
    )
    (net (code "62") (name "unconnected-(U1-IO_25_35-PadJ5)") (class "Default")
      (node (ref "U1") (pin "J5") (pinfunction "IO_25_35_J5") (pintype "passive"))
    )
    (net (code "63") (name "unconnected-(U1-IO_L1N_T0_34-PadM1)") (class "Default")
      (node (ref "U1") (pin "M1") (pinfunction "IO_L1N_T0_34_M1") (pintype "passive"))
    )
    (net (code "64") (name "unconnected-(U1-IO_L1N_T0_AD0N_15-PadC14)") (class "Default")
      (node (ref "U1") (pin "C14") (pinfunction "IO_L1N_T0_AD0N_15_C14") (pintype "passive"))
    )
    (net (code "65") (name "unconnected-(U1-IO_L1N_T0_AD4N_35-PadC5)") (class "Default")
      (node (ref "U1") (pin "C5") (pinfunction "IO_L1N_T0_AD4N_35_C5") (pintype "passive"))
    )
    (net (code "66") (name "unconnected-(U1-IO_L1P_T0_34-PadL1)") (class "Default")
      (node (ref "U1") (pin "L1") (pinfunction "IO_L1P_T0_34_L1") (pintype "passive"))
    )
    (net (code "67") (name "unconnected-(U1-IO_L1P_T0_AD0P_15-PadD14)") (class "Default")
      (node (ref "U1") (pin "D14") (pinfunction "IO_L1P_T0_AD0P_15_D14") (pintype "passive"))
    )
    (net (code "68") (name "unconnected-(U1-IO_L1P_T0_AD4P_35-PadC6)") (class "Default")
      (node (ref "U1") (pin "C6") (pinfunction "IO_L1P_T0_AD4P_35_C6") (pintype "passive"))
    )
    (net (code "69") (name "unconnected-(U1-IO_L2N_T0_34-PadL3)") (class "Default")
      (node (ref "U1") (pin "L3") (pinfunction "IO_L2N_T0_34_L3") (pintype "passive"))
    )
    (net (code "70") (name "unconnected-(U1-IO_L2N_T0_AD8N_15-PadB14)") (class "Default")
      (node (ref "U1") (pin "B14") (pinfunction "IO_L2N_T0_AD8N_15_B14") (pintype "passive"))
    )
    (net (code "71") (name "unconnected-(U1-IO_L2N_T0_AD12N_35-PadB6)") (class "Default")
      (node (ref "U1") (pin "B6") (pinfunction "IO_L2N_T0_AD12N_35_B6") (pintype "passive"))
    )
    (net (code "72") (name "unconnected-(U1-IO_L2P_T0_34-PadK3)") (class "Default")
      (node (ref "U1") (pin "K3") (pinfunction "IO_L2P_T0_34_K3") (pintype "passive"))
    )
    (net (code "73") (name "unconnected-(U1-IO_L2P_T0_AD8P_15-PadB13)") (class "Default")
      (node (ref "U1") (pin "B13") (pinfunction "IO_L2P_T0_AD8P_15_B13") (pintype "passive"))
    )
    (net (code "74") (name "unconnected-(U1-IO_L2P_T0_AD12P_35-PadB7)") (class "Default")
      (node (ref "U1") (pin "B7") (pinfunction "IO_L2P_T0_AD12P_35_B7") (pintype "passive"))
    )
    (net (code "75") (name "unconnected-(U1-IO_L3N_T0_DQS_34-PadN1)") (class "Default")
      (node (ref "U1") (pin "N1") (pinfunction "IO_L3N_T0_DQS_34_N1") (pintype "passive"))
    )
    (net (code "76") (name "unconnected-(U1-IO_L3N_T0_DQS_AD1N_15-PadB12)") (class "Default")
      (node (ref "U1") (pin "B12") (pinfunction "IO_L3N_T0_DQS_AD1N_15_B12") (pintype "passive"))
    )
    (net (code "77") (name "unconnected-(U1-IO_L3N_T0_DQS_AD5N_35-PadA5)") (class "Default")
      (node (ref "U1") (pin "A5") (pinfunction "IO_L3N_T0_DQS_AD5N_35_A5") (pintype "passive"))
    )
    (net (code "78") (name "unconnected-(U1-IO_L3N_T0_DQS_EMCCLK_14-PadL16)") (class "Default")
      (node (ref "U1") (pin "L16") (pinfunction "IO_L3N_T0_DQS_EMCCLK_14_L16") (pintype "passive"))
    )
    (net (code "79") (name "unconnected-(U1-IO_L3P_T0_DQS_34-PadN2)") (class "Default")
      (node (ref "U1") (pin "N2") (pinfunction "IO_L3P_T0_DQS_34_N2") (pintype "passive"))
    )
    (net (code "80") (name "unconnected-(U1-IO_L3P_T0_DQS_AD1P_15-PadC12)") (class "Default")
      (node (ref "U1") (pin "C12") (pinfunction "IO_L3P_T0_DQS_AD1P_15_C12") (pintype "passive"))
    )
    (net (code "81") (name "unconnected-(U1-IO_L3P_T0_DQS_AD5P_35-PadA6)") (class "Default")
      (node (ref "U1") (pin "A6") (pinfunction "IO_L3P_T0_DQS_AD5P_35_A6") (pintype "passive"))
    )
    (net (code "82") (name "unconnected-(U1-IO_L3P_T0_DQS_PUDC_B_14-PadL15)") (class "Default")
      (node (ref "U1") (pin "L15") (pinfunction "IO_L3P_T0_DQS_PUDC_B_14_L15") (pintype "passive"))
    )
    (net (code "83") (name "unconnected-(U1-IO_L4N_T0_34-PadM2)") (class "Default")
      (node (ref "U1") (pin "M2") (pinfunction "IO_L4N_T0_34_M2") (pintype "passive"))
    )
    (net (code "84") (name "unconnected-(U1-IO_L4N_T0_35-PadC7)") (class "Default")
      (node (ref "U1") (pin "C7") (pinfunction "IO_L4N_T0_35_C7") (pintype "passive"))
    )
    (net (code "85") (name "unconnected-(U1-IO_L4N_T0_D05_14-PadM18)") (class "Default")
      (node (ref "U1") (pin "M18") (pinfunction "IO_L4N_T0_D05_14_M18") (pintype "passive"))
    )
    (net (code "86") (name "unconnected-(U1-IO_L4P_T0_34-PadM3)") (class "Default")
      (node (ref "U1") (pin "M3") (pinfunction "IO_L4P_T0_34_M3") (pintype "passive"))
    )
    (net (code "87") (name "unconnected-(U1-IO_L4P_T0_35-PadD8)") (class "Default")
      (node (ref "U1") (pin "D8") (pinfunction "IO_L4P_T0_35_D8") (pintype "passive"))
    )
    (net (code "88") (name "unconnected-(U1-IO_L4P_T0_D04_14-PadL18)") (class "Default")
      (node (ref "U1") (pin "L18") (pinfunction "IO_L4P_T0_D04_14_L18") (pintype "passive"))
    )
    (net (code "89") (name "unconnected-(U1-IO_L5N_T0_34-PadL4)") (class "Default")
      (node (ref "U1") (pin "L4") (pinfunction "IO_L5N_T0_34_L4") (pintype "passive"))
    )
    (net (code "90") (name "unconnected-(U1-IO_L5N_T0_AD9N_15-PadF14)") (class "Default")
      (node (ref "U1") (pin "F14") (pinfunction "IO_L5N_T0_AD9N_15_F14") (pintype "passive"))
    )
    (net (code "91") (name "unconnected-(U1-IO_L5N_T0_AD13N_35-PadE5)") (class "Default")
      (node (ref "U1") (pin "E5") (pinfunction "IO_L5N_T0_AD13N_35_E5") (pintype "passive"))
    )
    (net (code "92") (name "unconnected-(U1-IO_L5N_T0_D07_14-PadR13)") (class "Default")
      (node (ref "U1") (pin "R13") (pinfunction "IO_L5N_T0_D07_14_R13") (pintype "passive"))
    )
    (net (code "93") (name "unconnected-(U1-IO_L5P_T0_34-PadK5)") (class "Default")
      (node (ref "U1") (pin "K5") (pinfunction "IO_L5P_T0_34_K5") (pintype "passive"))
    )
    (net (code "94") (name "unconnected-(U1-IO_L5P_T0_AD9P_15-PadF13)") (class "Default")
      (node (ref "U1") (pin "F13") (pinfunction "IO_L5P_T0_AD9P_15_F13") (pintype "passive"))
    )
    (net (code "95") (name "unconnected-(U1-IO_L5P_T0_AD13P_35-PadE6)") (class "Default")
      (node (ref "U1") (pin "E6") (pinfunction "IO_L5P_T0_AD13P_35_E6") (pintype "passive"))
    )
    (net (code "96") (name "unconnected-(U1-IO_L5P_T0_D06_14-PadR12)") (class "Default")
      (node (ref "U1") (pin "R12") (pinfunction "IO_L5P_T0_D06_14_R12") (pintype "passive"))
    )
    (net (code "97") (name "unconnected-(U1-IO_L6N_T0_D08_VREF_14-PadM13)") (class "Default")
      (node (ref "U1") (pin "M13") (pinfunction "IO_L6N_T0_D08_VREF_14_M13") (pintype "passive"))
    )
    (net (code "98") (name "unconnected-(U1-IO_L6N_T0_VREF_15-PadD13)") (class "Default")
      (node (ref "U1") (pin "D13") (pinfunction "IO_L6N_T0_VREF_15_D13") (pintype "passive"))
    )
    (net (code "99") (name "unconnected-(U1-IO_L6N_T0_VREF_16-PadD9)") (class "Default")
      (node (ref "U1") (pin "D9") (pinfunction "IO_L6N_T0_VREF_16_D9") (pintype "passive"))
    )
    (net (code "100") (name "unconnected-(U1-IO_L6N_T0_VREF_34-PadL5)") (class "Default")
      (node (ref "U1") (pin "L5") (pinfunction "IO_L6N_T0_VREF_34_L5") (pintype "passive"))
    )
    (net (code "101") (name "unconnected-(U1-IO_L6N_T0_VREF_35-PadD7)") (class "Default")
      (node (ref "U1") (pin "D7") (pinfunction "IO_L6N_T0_VREF_35_D7") (pintype "passive"))
    )
    (net (code "102") (name "unconnected-(U1-IO_L6P_T0_34-PadL6)") (class "Default")
      (node (ref "U1") (pin "L6") (pinfunction "IO_L6P_T0_34_L6") (pintype "passive"))
    )
    (net (code "103") (name "unconnected-(U1-IO_L6P_T0_35-PadE7)") (class "Default")
      (node (ref "U1") (pin "E7") (pinfunction "IO_L6P_T0_35_E7") (pintype "passive"))
    )
    (net (code "104") (name "unconnected-(U1-IO_L7N_T1_34-PadV1)") (class "Default")
      (node (ref "U1") (pin "V1") (pinfunction "IO_L7N_T1_34_V1") (pintype "passive"))
    )
    (net (code "105") (name "unconnected-(U1-IO_L7N_T1_AD2N_15-PadB17)") (class "Default")
      (node (ref "U1") (pin "B17") (pinfunction "IO_L7N_T1_AD2N_15_B17") (pintype "passive"))
    )
    (net (code "106") (name "unconnected-(U1-IO_L7N_T1_AD6N_35-PadB4)") (class "Default")
      (node (ref "U1") (pin "B4") (pinfunction "IO_L7N_T1_AD6N_35_B4") (pintype "passive"))
    )
    (net (code "107") (name "unconnected-(U1-IO_L7N_T1_D10_14-PadT18)") (class "Default")
      (node (ref "U1") (pin "T18") (pinfunction "IO_L7N_T1_D10_14_T18") (pintype "passive"))
    )
    (net (code "108") (name "unconnected-(U1-IO_L7P_T1_34-PadU1)") (class "Default")
      (node (ref "U1") (pin "U1") (pinfunction "IO_L7P_T1_34_U1") (pintype "passive"))
    )
    (net (code "109") (name "unconnected-(U1-IO_L7P_T1_AD2P_15-PadB16)") (class "Default")
      (node (ref "U1") (pin "B16") (pinfunction "IO_L7P_T1_AD2P_15_B16") (pintype "passive"))
    )
    (net (code "110") (name "unconnected-(U1-IO_L7P_T1_AD6P_35-PadC4)") (class "Default")
      (node (ref "U1") (pin "C4") (pinfunction "IO_L7P_T1_AD6P_35_C4") (pintype "passive"))
    )
    (net (code "111") (name "unconnected-(U1-IO_L7P_T1_D09_14-PadR18)") (class "Default")
      (node (ref "U1") (pin "R18") (pinfunction "IO_L7P_T1_D09_14_R18") (pintype "passive"))
    )
    (net (code "112") (name "unconnected-(U1-IO_L8N_T1_34-PadU3)") (class "Default")
      (node (ref "U1") (pin "U3") (pinfunction "IO_L8N_T1_34_U3") (pintype "passive"))
    )
    (net (code "113") (name "unconnected-(U1-IO_L8N_T1_AD10N_15-PadA16)") (class "Default")
      (node (ref "U1") (pin "A16") (pinfunction "IO_L8N_T1_AD10N_15_A16") (pintype "passive"))
    )
    (net (code "114") (name "unconnected-(U1-IO_L8N_T1_AD14N_35-PadA3)") (class "Default")
      (node (ref "U1") (pin "A3") (pinfunction "IO_L8N_T1_AD14N_35_A3") (pintype "passive"))
    )
    (net (code "115") (name "unconnected-(U1-IO_L8N_T1_D12_14-PadP14)") (class "Default")
      (node (ref "U1") (pin "P14") (pinfunction "IO_L8N_T1_D12_14_P14") (pintype "passive"))
    )
    (net (code "116") (name "unconnected-(U1-IO_L8P_T1_34-PadU4)") (class "Default")
      (node (ref "U1") (pin "U4") (pinfunction "IO_L8P_T1_34_U4") (pintype "passive"))
    )
    (net (code "117") (name "unconnected-(U1-IO_L8P_T1_AD10P_15-PadA15)") (class "Default")
      (node (ref "U1") (pin "A15") (pinfunction "IO_L8P_T1_AD10P_15_A15") (pintype "passive"))
    )
    (net (code "118") (name "unconnected-(U1-IO_L8P_T1_AD14P_35-PadA4)") (class "Default")
      (node (ref "U1") (pin "A4") (pinfunction "IO_L8P_T1_AD14P_35_A4") (pintype "passive"))
    )
    (net (code "119") (name "unconnected-(U1-IO_L8P_T1_D11_14-PadN14)") (class "Default")
      (node (ref "U1") (pin "N14") (pinfunction "IO_L8P_T1_D11_14_N14") (pintype "passive"))
    )
    (net (code "120") (name "unconnected-(U1-IO_L9N_T1_DQS_34-PadV2)") (class "Default")
      (node (ref "U1") (pin "V2") (pinfunction "IO_L9N_T1_DQS_34_V2") (pintype "passive"))
    )
    (net (code "121") (name "unconnected-(U1-IO_L9N_T1_DQS_AD3N_15-PadA14)") (class "Default")
      (node (ref "U1") (pin "A14") (pinfunction "IO_L9N_T1_DQS_AD3N_15_A14") (pintype "passive"))
    )
    (net (code "122") (name "unconnected-(U1-IO_L9N_T1_DQS_AD7N_35-PadA1)") (class "Default")
      (node (ref "U1") (pin "A1") (pinfunction "IO_L9N_T1_DQS_AD7N_35_A1") (pintype "passive"))
    )
    (net (code "123") (name "unconnected-(U1-IO_L9N_T1_DQS_D13_14-PadP18)") (class "Default")
      (node (ref "U1") (pin "P18") (pinfunction "IO_L9N_T1_DQS_D13_14_P18") (pintype "passive"))
    )
    (net (code "124") (name "unconnected-(U1-IO_L9P_T1_DQS_14-PadN17)") (class "Default")
      (node (ref "U1") (pin "N17") (pinfunction "IO_L9P_T1_DQS_14_N17") (pintype "passive"))
    )
    (net (code "125") (name "unconnected-(U1-IO_L9P_T1_DQS_34-PadU2)") (class "Default")
      (node (ref "U1") (pin "U2") (pinfunction "IO_L9P_T1_DQS_34_U2") (pintype "passive"))
    )
    (net (code "126") (name "unconnected-(U1-IO_L9P_T1_DQS_AD3P_15-PadA13)") (class "Default")
      (node (ref "U1") (pin "A13") (pinfunction "IO_L9P_T1_DQS_AD3P_15_A13") (pintype "passive"))
    )
    (net (code "127") (name "unconnected-(U1-IO_L9P_T1_DQS_AD7P_35-PadB1)") (class "Default")
      (node (ref "U1") (pin "B1") (pinfunction "IO_L9P_T1_DQS_AD7P_35_B1") (pintype "passive"))
    )
    (net (code "128") (name "unconnected-(U1-IO_L10N_T1_34-PadV4)") (class "Default")
      (node (ref "U1") (pin "V4") (pinfunction "IO_L10N_T1_34_V4") (pintype "passive"))
    )
    (net (code "129") (name "unconnected-(U1-IO_L10N_T1_AD11N_15-PadA18)") (class "Default")
      (node (ref "U1") (pin "A18") (pinfunction "IO_L10N_T1_AD11N_15_A18") (pintype "passive"))
    )
    (net (code "130") (name "unconnected-(U1-IO_L10N_T1_AD15N_35-PadB2)") (class "Default")
      (node (ref "U1") (pin "B2") (pinfunction "IO_L10N_T1_AD15N_35_B2") (pintype "passive"))
    )
    (net (code "131") (name "unconnected-(U1-IO_L10N_T1_D15_14-PadM17)") (class "Default")
      (node (ref "U1") (pin "M17") (pinfunction "IO_L10N_T1_D15_14_M17") (pintype "passive"))
    )
    (net (code "132") (name "unconnected-(U1-IO_L10P_T1_34-PadV5)") (class "Default")
      (node (ref "U1") (pin "V5") (pinfunction "IO_L10P_T1_34_V5") (pintype "passive"))
    )
    (net (code "133") (name "unconnected-(U1-IO_L10P_T1_AD11P_15-PadB18)") (class "Default")
      (node (ref "U1") (pin "B18") (pinfunction "IO_L10P_T1_AD11P_15_B18") (pintype "passive"))
    )
    (net (code "134") (name "unconnected-(U1-IO_L10P_T1_AD15P_35-PadB3)") (class "Default")
      (node (ref "U1") (pin "B3") (pinfunction "IO_L10P_T1_AD15P_35_B3") (pintype "passive"))
    )
    (net (code "135") (name "unconnected-(U1-IO_L10P_T1_D14_14-PadM16)") (class "Default")
      (node (ref "U1") (pin "M16") (pinfunction "IO_L10P_T1_D14_14_M16") (pintype "passive"))
    )
    (net (code "136") (name "unconnected-(U1-IO_L11N_T1_SRCC_14-PadN16)") (class "Default")
      (node (ref "U1") (pin "N16") (pinfunction "IO_L11N_T1_SRCC_14_N16") (pintype "passive"))
    )
    (net (code "137") (name "unconnected-(U1-IO_L11N_T1_SRCC_16-PadB9)") (class "Default")
      (node (ref "U1") (pin "B9") (pinfunction "IO_L11N_T1_SRCC_16_B9") (pintype "passive"))
    )
    (net (code "138") (name "unconnected-(U1-IO_L11N_T1_SRCC_34-PadT3)") (class "Default")
      (node (ref "U1") (pin "T3") (pinfunction "IO_L11N_T1_SRCC_34_T3") (pintype "passive"))
    )
    (net (code "139") (name "unconnected-(U1-IO_L11N_T1_SRCC_35-PadD4)") (class "Default")
      (node (ref "U1") (pin "D4") (pinfunction "IO_L11N_T1_SRCC_35_D4") (pintype "passive"))
    )
    (net (code "140") (name "unconnected-(U1-IO_L11P_T1_SRCC_14-PadN15)") (class "Default")
      (node (ref "U1") (pin "N15") (pinfunction "IO_L11P_T1_SRCC_14_N15") (pintype "passive"))
    )
    (net (code "141") (name "unconnected-(U1-IO_L11P_T1_SRCC_16-PadC9)") (class "Default")
      (node (ref "U1") (pin "C9") (pinfunction "IO_L11P_T1_SRCC_16_C9") (pintype "passive"))
    )
    (net (code "142") (name "unconnected-(U1-IO_L11P_T1_SRCC_34-PadR3)") (class "Default")
      (node (ref "U1") (pin "R3") (pinfunction "IO_L11P_T1_SRCC_34_R3") (pintype "passive"))
    )
    (net (code "143") (name "unconnected-(U1-IO_L11P_T1_SRCC_35-PadD5)") (class "Default")
      (node (ref "U1") (pin "D5") (pinfunction "IO_L11P_T1_SRCC_35_D5") (pintype "passive"))
    )
    (net (code "144") (name "unconnected-(U1-IO_L12N_T1_MRCC_14-PadR17)") (class "Default")
      (node (ref "U1") (pin "R17") (pinfunction "IO_L12N_T1_MRCC_14_R17") (pintype "passive"))
    )
    (net (code "145") (name "unconnected-(U1-IO_L12N_T1_MRCC_16-PadA8)") (class "Default")
      (node (ref "U1") (pin "A8") (pinfunction "IO_L12N_T1_MRCC_16_A8") (pintype "passive"))
    )
    (net (code "146") (name "unconnected-(U1-IO_L12N_T1_MRCC_34-PadT4)") (class "Default")
      (node (ref "U1") (pin "T4") (pinfunction "IO_L12N_T1_MRCC_34_T4") (pintype "passive"))
    )
    (net (code "147") (name "unconnected-(U1-IO_L12N_T1_MRCC_35-PadD3)") (class "Default")
      (node (ref "U1") (pin "D3") (pinfunction "IO_L12N_T1_MRCC_35_D3") (pintype "passive"))
    )
    (net (code "148") (name "unconnected-(U1-IO_L12P_T1_MRCC_16-PadB8)") (class "Default")
      (node (ref "U1") (pin "B8") (pinfunction "IO_L12P_T1_MRCC_16_B8") (pintype "passive"))
    )
    (net (code "149") (name "unconnected-(U1-IO_L12P_T1_MRCC_34-PadT5)") (class "Default")
      (node (ref "U1") (pin "T5") (pinfunction "IO_L12P_T1_MRCC_34_T5") (pintype "passive"))
    )
    (net (code "150") (name "unconnected-(U1-IO_L12P_T1_MRCC_35-PadE3)") (class "Default")
      (node (ref "U1") (pin "E3") (pinfunction "IO_L12P_T1_MRCC_35_E3") (pintype "passive"))
    )
    (net (code "151") (name "unconnected-(U1-IO_L13N_T2_MRCC_14-PadR15)") (class "Default")
      (node (ref "U1") (pin "R15") (pinfunction "IO_L13N_T2_MRCC_14_R15") (pintype "passive"))
    )
    (net (code "152") (name "unconnected-(U1-IO_L13N_T2_MRCC_16-PadC10)") (class "Default")
      (node (ref "U1") (pin "C10") (pinfunction "IO_L13N_T2_MRCC_16_C10") (pintype "passive"))
    )
    (net (code "153") (name "unconnected-(U1-IO_L13N_T2_MRCC_34-PadP5)") (class "Default")
      (node (ref "U1") (pin "P5") (pinfunction "IO_L13N_T2_MRCC_34_P5") (pintype "passive"))
    )
    (net (code "154") (name "unconnected-(U1-IO_L13N_T2_MRCC_35-PadF3)") (class "Default")
      (node (ref "U1") (pin "F3") (pinfunction "IO_L13N_T2_MRCC_35_F3") (pintype "passive"))
    )
    (net (code "155") (name "unconnected-(U1-IO_L13P_T2_MRCC_14-PadP15)") (class "Default")
      (node (ref "U1") (pin "P15") (pinfunction "IO_L13P_T2_MRCC_14_P15") (pintype "passive"))
    )
    (net (code "156") (name "unconnected-(U1-IO_L13P_T2_MRCC_16-PadC11)") (class "Default")
      (node (ref "U1") (pin "C11") (pinfunction "IO_L13P_T2_MRCC_16_C11") (pintype "passive"))
    )
    (net (code "157") (name "unconnected-(U1-IO_L13P_T2_MRCC_34-PadN5)") (class "Default")
      (node (ref "U1") (pin "N5") (pinfunction "IO_L13P_T2_MRCC_34_N5") (pintype "passive"))
    )
    (net (code "158") (name "unconnected-(U1-IO_L13P_T2_MRCC_35-PadF4)") (class "Default")
      (node (ref "U1") (pin "F4") (pinfunction "IO_L13P_T2_MRCC_35_F4") (pintype "passive"))
    )
    (net (code "159") (name "unconnected-(U1-IO_L14N_T2_SRCC_14-PadT15)") (class "Default")
      (node (ref "U1") (pin "T15") (pinfunction "IO_L14N_T2_SRCC_14_T15") (pintype "passive"))
    )
    (net (code "160") (name "unconnected-(U1-IO_L14N_T2_SRCC_16-PadA9)") (class "Default")
      (node (ref "U1") (pin "A9") (pinfunction "IO_L14N_T2_SRCC_16_A9") (pintype "passive"))
    )
    (net (code "161") (name "unconnected-(U1-IO_L14N_T2_SRCC_34-PadP3)") (class "Default")
      (node (ref "U1") (pin "P3") (pinfunction "IO_L14N_T2_SRCC_34_P3") (pintype "passive"))
    )
    (net (code "162") (name "unconnected-(U1-IO_L14N_T2_SRCC_35-PadD2)") (class "Default")
      (node (ref "U1") (pin "D2") (pinfunction "IO_L14N_T2_SRCC_35_D2") (pintype "passive"))
    )
    (net (code "163") (name "unconnected-(U1-IO_L14P_T2_SRCC_14-PadT14)") (class "Default")
      (node (ref "U1") (pin "T14") (pinfunction "IO_L14P_T2_SRCC_14_T14") (pintype "passive"))
    )
    (net (code "164") (name "unconnected-(U1-IO_L14P_T2_SRCC_16-PadA10)") (class "Default")
      (node (ref "U1") (pin "A10") (pinfunction "IO_L14P_T2_SRCC_16_A10") (pintype "passive"))
    )
    (net (code "165") (name "unconnected-(U1-IO_L14P_T2_SRCC_34-PadP4)") (class "Default")
      (node (ref "U1") (pin "P4") (pinfunction "IO_L14P_T2_SRCC_34_P4") (pintype "passive"))
    )
    (net (code "166") (name "unconnected-(U1-IO_L14P_T2_SRCC_35-PadE2)") (class "Default")
      (node (ref "U1") (pin "E2") (pinfunction "IO_L14P_T2_SRCC_35_E2") (pintype "passive"))
    )
    (net (code "167") (name "unconnected-(U1-IO_L15N_T2_DQS_34-PadR2)") (class "Default")
      (node (ref "U1") (pin "R2") (pinfunction "IO_L15N_T2_DQS_34_R2") (pintype "passive"))
    )
    (net (code "168") (name "unconnected-(U1-IO_L15N_T2_DQS_35-PadG2)") (class "Default")
      (node (ref "U1") (pin "G2") (pinfunction "IO_L15N_T2_DQS_35_G2") (pintype "passive"))
    )
    (net (code "169") (name "unconnected-(U1-IO_L15N_T2_DQS_ADV_B_15-PadG14)") (class "Default")
      (node (ref "U1") (pin "G14") (pinfunction "IO_L15N_T2_DQS_ADV_B_15_G14") (pintype "passive"))
    )
    (net (code "170") (name "unconnected-(U1-IO_L15N_T2_DQS_DOUT_CSO_B_14-PadT16)") (class "Default")
      (node (ref "U1") (pin "T16") (pinfunction "IO_L15N_T2_DQS_DOUT_CSO_B_14_T16") (pintype "passive"))
    )
    (net (code "171") (name "unconnected-(U1-IO_L15P_T2_DQS_34-PadP2)") (class "Default")
      (node (ref "U1") (pin "P2") (pinfunction "IO_L15P_T2_DQS_34_P2") (pintype "passive"))
    )
    (net (code "172") (name "unconnected-(U1-IO_L15P_T2_DQS_35-PadH2)") (class "Default")
      (node (ref "U1") (pin "H2") (pinfunction "IO_L15P_T2_DQS_35_H2") (pintype "passive"))
    )
    (net (code "173") (name "unconnected-(U1-IO_L15P_T2_DQS_RDWR_B_14-PadR16)") (class "Default")
      (node (ref "U1") (pin "R16") (pinfunction "IO_L15P_T2_DQS_RDWR_B_14_R16") (pintype "passive"))
    )
    (net (code "174") (name "unconnected-(U1-IO_L16N_T2_34-PadN4)") (class "Default")
      (node (ref "U1") (pin "N4") (pinfunction "IO_L16N_T2_34_N4") (pintype "passive"))
    )
    (net (code "175") (name "unconnected-(U1-IO_L16N_T2_35-PadC1)") (class "Default")
      (node (ref "U1") (pin "C1") (pinfunction "IO_L16N_T2_35_C1") (pintype "passive"))
    )
    (net (code "176") (name "unconnected-(U1-IO_L16N_T2_A15_D31_14-PadV16)") (class "Default")
      (node (ref "U1") (pin "V16") (pinfunction "IO_L16N_T2_A15_D31_14_V16") (pintype "passive"))
    )
    (net (code "177") (name "unconnected-(U1-IO_L16N_T2_A27_15-PadD17)") (class "Default")
      (node (ref "U1") (pin "D17") (pinfunction "IO_L16N_T2_A27_15_D17") (pintype "passive"))
    )
    (net (code "178") (name "unconnected-(U1-IO_L16P_T2_34-PadM4)") (class "Default")
      (node (ref "U1") (pin "M4") (pinfunction "IO_L16P_T2_34_M4") (pintype "passive"))
    )
    (net (code "179") (name "unconnected-(U1-IO_L16P_T2_35-PadC2)") (class "Default")
      (node (ref "U1") (pin "C2") (pinfunction "IO_L16P_T2_35_C2") (pintype "passive"))
    )
    (net (code "180") (name "unconnected-(U1-IO_L16P_T2_A28_15-PadE17)") (class "Default")
      (node (ref "U1") (pin "E17") (pinfunction "IO_L16P_T2_A28_15_E17") (pintype "passive"))
    )
    (net (code "181") (name "unconnected-(U1-IO_L16P_T2_CSI_B_14-PadV15)") (class "Default")
      (node (ref "U1") (pin "V15") (pinfunction "IO_L16P_T2_CSI_B_14_V15") (pintype "passive"))
    )
    (net (code "182") (name "unconnected-(U1-IO_L17N_T2_34-PadT1)") (class "Default")
      (node (ref "U1") (pin "T1") (pinfunction "IO_L17N_T2_34_T1") (pintype "passive"))
    )
    (net (code "183") (name "unconnected-(U1-IO_L17N_T2_35-PadG1)") (class "Default")
      (node (ref "U1") (pin "G1") (pinfunction "IO_L17N_T2_35_G1") (pintype "passive"))
    )
    (net (code "184") (name "unconnected-(U1-IO_L17N_T2_A13_D29_14-PadU18)") (class "Default")
      (node (ref "U1") (pin "U18") (pinfunction "IO_L17N_T2_A13_D29_14_U18") (pintype "passive"))
    )
    (net (code "185") (name "unconnected-(U1-IO_L17N_T2_A25_15-PadJ13)") (class "Default")
      (node (ref "U1") (pin "J13") (pinfunction "IO_L17N_T2_A25_15_J13") (pintype "passive"))
    )
    (net (code "186") (name "unconnected-(U1-IO_L17P_T2_34-PadR1)") (class "Default")
      (node (ref "U1") (pin "R1") (pinfunction "IO_L17P_T2_34_R1") (pintype "passive"))
    )
    (net (code "187") (name "unconnected-(U1-IO_L17P_T2_35-PadH1)") (class "Default")
      (node (ref "U1") (pin "H1") (pinfunction "IO_L17P_T2_35_H1") (pintype "passive"))
    )
    (net (code "188") (name "unconnected-(U1-IO_L17P_T2_A14_D30_14-PadU17)") (class "Default")
      (node (ref "U1") (pin "U17") (pinfunction "IO_L17P_T2_A14_D30_14_U17") (pintype "passive"))
    )
    (net (code "189") (name "unconnected-(U1-IO_L17P_T2_A26_15-PadK13)") (class "Default")
      (node (ref "U1") (pin "K13") (pinfunction "IO_L17P_T2_A26_15_K13") (pintype "passive"))
    )
    (net (code "190") (name "unconnected-(U1-IO_L18N_T2_34-PadN6)") (class "Default")
      (node (ref "U1") (pin "N6") (pinfunction "IO_L18N_T2_34_N6") (pintype "passive"))
    )
    (net (code "191") (name "unconnected-(U1-IO_L18N_T2_35-PadE1)") (class "Default")
      (node (ref "U1") (pin "E1") (pinfunction "IO_L18N_T2_35_E1") (pintype "passive"))
    )
    (net (code "192") (name "unconnected-(U1-IO_L18N_T2_A11_D27_14-PadV17)") (class "Default")
      (node (ref "U1") (pin "V17") (pinfunction "IO_L18N_T2_A11_D27_14_V17") (pintype "passive"))
    )
    (net (code "193") (name "unconnected-(U1-IO_L18N_T2_A23_15-PadG17)") (class "Default")
      (node (ref "U1") (pin "G17") (pinfunction "IO_L18N_T2_A23_15_G17") (pintype "passive"))
    )
    (net (code "194") (name "unconnected-(U1-IO_L18P_T2_34-PadM6)") (class "Default")
      (node (ref "U1") (pin "M6") (pinfunction "IO_L18P_T2_34_M6") (pintype "passive"))
    )
    (net (code "195") (name "unconnected-(U1-IO_L18P_T2_35-PadF1)") (class "Default")
      (node (ref "U1") (pin "F1") (pinfunction "IO_L18P_T2_35_F1") (pintype "passive"))
    )
    (net (code "196") (name "unconnected-(U1-IO_L18P_T2_A12_D28_14-PadU16)") (class "Default")
      (node (ref "U1") (pin "U16") (pinfunction "IO_L18P_T2_A12_D28_14_U16") (pintype "passive"))
    )
    (net (code "197") (name "unconnected-(U1-IO_L18P_T2_A24_15-PadH17)") (class "Default")
      (node (ref "U1") (pin "H17") (pinfunction "IO_L18P_T2_A24_15_H17") (pintype "passive"))
    )
    (net (code "198") (name "unconnected-(U1-IO_L19N_T3_A09_D25_VREF_14-PadU11)") (class "Default")
      (node (ref "U1") (pin "U11") (pinfunction "IO_L19N_T3_A09_D25_VREF_14_U11") (pintype "passive"))
    )
    (net (code "199") (name "unconnected-(U1-IO_L19N_T3_A21_VREF_15-PadH15)") (class "Default")
      (node (ref "U1") (pin "H15") (pinfunction "IO_L19N_T3_A21_VREF_15_H15") (pintype "passive"))
    )
    (net (code "200") (name "unconnected-(U1-IO_L19N_T3_VREF_16-PadD10)") (class "Default")
      (node (ref "U1") (pin "D10") (pinfunction "IO_L19N_T3_VREF_16_D10") (pintype "passive"))
    )
    (net (code "201") (name "unconnected-(U1-IO_L19N_T3_VREF_34-PadR5)") (class "Default")
      (node (ref "U1") (pin "R5") (pinfunction "IO_L19N_T3_VREF_34_R5") (pintype "passive"))
    )
    (net (code "202") (name "unconnected-(U1-IO_L19N_T3_VREF_35-PadF6)") (class "Default")
      (node (ref "U1") (pin "F6") (pinfunction "IO_L19N_T3_VREF_35_F6") (pintype "passive"))
    )
    (net (code "203") (name "unconnected-(U1-IO_L19P_T3_34-PadR6)") (class "Default")
      (node (ref "U1") (pin "R6") (pinfunction "IO_L19P_T3_34_R6") (pintype "passive"))
    )
    (net (code "204") (name "unconnected-(U1-IO_L19P_T3_35-PadG6)") (class "Default")
      (node (ref "U1") (pin "G6") (pinfunction "IO_L19P_T3_35_G6") (pintype "passive"))
    )
    (net (code "205") (name "unconnected-(U1-IO_L19P_T3_A10_D26_14-PadT11)") (class "Default")
      (node (ref "U1") (pin "T11") (pinfunction "IO_L19P_T3_A10_D26_14_T11") (pintype "passive"))
    )
    (net (code "206") (name "unconnected-(U1-IO_L19P_T3_A22_15-PadJ14)") (class "Default")
      (node (ref "U1") (pin "J14") (pinfunction "IO_L19P_T3_A22_15_J14") (pintype "passive"))
    )
    (net (code "207") (name "unconnected-(U1-IO_L20N_T3_34-PadV6)") (class "Default")
      (node (ref "U1") (pin "V6") (pinfunction "IO_L20N_T3_34_V6") (pintype "passive"))
    )
    (net (code "208") (name "unconnected-(U1-IO_L20N_T3_35-PadG3)") (class "Default")
      (node (ref "U1") (pin "G3") (pinfunction "IO_L20N_T3_35_G3") (pintype "passive"))
    )
    (net (code "209") (name "unconnected-(U1-IO_L20N_T3_A07_D23_14-PadV12)") (class "Default")
      (node (ref "U1") (pin "V12") (pinfunction "IO_L20N_T3_A07_D23_14_V12") (pintype "passive"))
    )
    (net (code "210") (name "unconnected-(U1-IO_L20N_T3_A19_15-PadC17)") (class "Default")
      (node (ref "U1") (pin "C17") (pinfunction "IO_L20N_T3_A19_15_C17") (pintype "passive"))
    )
    (net (code "211") (name "unconnected-(U1-IO_L20P_T3_34-PadV7)") (class "Default")
      (node (ref "U1") (pin "V7") (pinfunction "IO_L20P_T3_34_V7") (pintype "passive"))
    )
    (net (code "212") (name "unconnected-(U1-IO_L20P_T3_35-PadG4)") (class "Default")
      (node (ref "U1") (pin "G4") (pinfunction "IO_L20P_T3_35_G4") (pintype "passive"))
    )
    (net (code "213") (name "unconnected-(U1-IO_L20P_T3_A08_D24_14-PadU12)") (class "Default")
      (node (ref "U1") (pin "U12") (pinfunction "IO_L20P_T3_A08_D24_14_U12") (pintype "passive"))
    )
    (net (code "214") (name "unconnected-(U1-IO_L20P_T3_A20_15-PadC16)") (class "Default")
      (node (ref "U1") (pin "C16") (pinfunction "IO_L20P_T3_A20_15_C16") (pintype "passive"))
    )
    (net (code "215") (name "unconnected-(U1-IO_L21N_T3_DQS_34-PadV9)") (class "Default")
      (node (ref "U1") (pin "V9") (pinfunction "IO_L21N_T3_DQS_34_V9") (pintype "passive"))
    )
    (net (code "216") (name "unconnected-(U1-IO_L21N_T3_DQS_35-PadH4)") (class "Default")
      (node (ref "U1") (pin "H4") (pinfunction "IO_L21N_T3_DQS_35_H4") (pintype "passive"))
    )
    (net (code "217") (name "unconnected-(U1-IO_L21N_T3_DQS_A06_D22_14-PadV11)") (class "Default")
      (node (ref "U1") (pin "V11") (pinfunction "IO_L21N_T3_DQS_A06_D22_14_V11") (pintype "passive"))
    )
    (net (code "218") (name "unconnected-(U1-IO_L21N_T3_DQS_A18_15-PadD18)") (class "Default")
      (node (ref "U1") (pin "D18") (pinfunction "IO_L21N_T3_DQS_A18_15_D18") (pintype "passive"))
    )
    (net (code "219") (name "unconnected-(U1-IO_L21P_T3_DQS_14-PadV10)") (class "Default")
      (node (ref "U1") (pin "V10") (pinfunction "IO_L21P_T3_DQS_14_V10") (pintype "passive"))
    )
    (net (code "220") (name "unconnected-(U1-IO_L21P_T3_DQS_34-PadU9)") (class "Default")
      (node (ref "U1") (pin "U9") (pinfunction "IO_L21P_T3_DQS_34_U9") (pintype "passive"))
    )
    (net (code "221") (name "unconnected-(U1-IO_L21P_T3_DQS_35-PadJ4)") (class "Default")
      (node (ref "U1") (pin "J4") (pinfunction "IO_L21P_T3_DQS_35_J4") (pintype "passive"))
    )
    (net (code "222") (name "unconnected-(U1-IO_L22N_T3_34-PadU6)") (class "Default")
      (node (ref "U1") (pin "U6") (pinfunction "IO_L22N_T3_34_U6") (pintype "passive"))
    )
    (net (code "223") (name "unconnected-(U1-IO_L22N_T3_35-PadJ2)") (class "Default")
      (node (ref "U1") (pin "J2") (pinfunction "IO_L22N_T3_35_J2") (pintype "passive"))
    )
    (net (code "224") (name "unconnected-(U1-IO_L22N_T3_A04_D20_14-PadV14)") (class "Default")
      (node (ref "U1") (pin "V14") (pinfunction "IO_L22N_T3_A04_D20_14_V14") (pintype "passive"))
    )
    (net (code "225") (name "unconnected-(U1-IO_L22N_T3_A16_15-PadF18)") (class "Default")
      (node (ref "U1") (pin "F18") (pinfunction "IO_L22N_T3_A16_15_F18") (pintype "passive"))
    )
    (net (code "226") (name "unconnected-(U1-IO_L22P_T3_34-PadU7)") (class "Default")
      (node (ref "U1") (pin "U7") (pinfunction "IO_L22P_T3_34_U7") (pintype "passive"))
    )
    (net (code "227") (name "unconnected-(U1-IO_L22P_T3_35-PadJ3)") (class "Default")
      (node (ref "U1") (pin "J3") (pinfunction "IO_L22P_T3_35_J3") (pintype "passive"))
    )
    (net (code "228") (name "unconnected-(U1-IO_L22P_T3_A05_D21_14-PadU14)") (class "Default")
      (node (ref "U1") (pin "U14") (pinfunction "IO_L22P_T3_A05_D21_14_U14") (pintype "passive"))
    )
    (net (code "229") (name "unconnected-(U1-IO_L22P_T3_A17_15-PadG18)") (class "Default")
      (node (ref "U1") (pin "G18") (pinfunction "IO_L22P_T3_A17_15_G18") (pintype "passive"))
    )
    (net (code "230") (name "unconnected-(U1-IO_L23N_T3_34-PadT6)") (class "Default")
      (node (ref "U1") (pin "T6") (pinfunction "IO_L23N_T3_34_T6") (pintype "passive"))
    )
    (net (code "231") (name "unconnected-(U1-IO_L23N_T3_35-PadK1)") (class "Default")
      (node (ref "U1") (pin "K1") (pinfunction "IO_L23N_T3_35_K1") (pintype "passive"))
    )
    (net (code "232") (name "unconnected-(U1-IO_L23N_T3_A02_D18_14-PadU13)") (class "Default")
      (node (ref "U1") (pin "U13") (pinfunction "IO_L23N_T3_A02_D18_14_U13") (pintype "passive"))
    )
    (net (code "233") (name "unconnected-(U1-IO_L23N_T3_FWE_B_15-PadJ18)") (class "Default")
      (node (ref "U1") (pin "J18") (pinfunction "IO_L23N_T3_FWE_B_15_J18") (pintype "passive"))
    )
    (net (code "234") (name "unconnected-(U1-IO_L23P_T3_34-PadR7)") (class "Default")
      (node (ref "U1") (pin "R7") (pinfunction "IO_L23P_T3_34_R7") (pintype "passive"))
    )
    (net (code "235") (name "unconnected-(U1-IO_L23P_T3_35-PadK2)") (class "Default")
      (node (ref "U1") (pin "K2") (pinfunction "IO_L23P_T3_35_K2") (pintype "passive"))
    )
    (net (code "236") (name "unconnected-(U1-IO_L23P_T3_A03_D19_14-PadT13)") (class "Default")
      (node (ref "U1") (pin "T13") (pinfunction "IO_L23P_T3_A03_D19_14_T13") (pintype "passive"))
    )
    (net (code "237") (name "unconnected-(U1-IO_L23P_T3_FOE_B_15-PadJ17)") (class "Default")
      (node (ref "U1") (pin "J17") (pinfunction "IO_L23P_T3_FOE_B_15_J17") (pintype "passive"))
    )
    (net (code "238") (name "unconnected-(U1-IO_L24N_T3_34-PadT8)") (class "Default")
      (node (ref "U1") (pin "T8") (pinfunction "IO_L24N_T3_34_T8") (pintype "passive"))
    )
    (net (code "239") (name "unconnected-(U1-IO_L24N_T3_35-PadH5)") (class "Default")
      (node (ref "U1") (pin "H5") (pinfunction "IO_L24N_T3_35_H5") (pintype "passive"))
    )
    (net (code "240") (name "unconnected-(U1-IO_L24N_T3_A00_D16_14-PadT10)") (class "Default")
      (node (ref "U1") (pin "T10") (pinfunction "IO_L24N_T3_A00_D16_14_T10") (pintype "passive"))
    )
    (net (code "241") (name "unconnected-(U1-IO_L24N_T3_RS0_15-PadJ15)") (class "Default")
      (node (ref "U1") (pin "J15") (pinfunction "IO_L24N_T3_RS0_15_J15") (pintype "passive"))
    )
    (net (code "242") (name "unconnected-(U1-IO_L24P_T3_34-PadR8)") (class "Default")
      (node (ref "U1") (pin "R8") (pinfunction "IO_L24P_T3_34_R8") (pintype "passive"))
    )
    (net (code "243") (name "unconnected-(U1-IO_L24P_T3_35-PadH6)") (class "Default")
      (node (ref "U1") (pin "H6") (pinfunction "IO_L24P_T3_35_H6") (pintype "passive"))
    )
    (net (code "244") (name "unconnected-(U1-IO_L24P_T3_A01_D17_14-PadT9)") (class "Default")
      (node (ref "U1") (pin "T9") (pinfunction "IO_L24P_T3_A01_D17_14_T9") (pintype "passive"))
    )
    (net (code "245") (name "unconnected-(U1-IO_L24P_T3_RS1_15-PadK15)") (class "Default")
      (node (ref "U1") (pin "K15") (pinfunction "IO_L24P_T3_RS1_15_K15") (pintype "passive"))
    )
    (net (code "246") (name "unconnected-(U1-VREFN_0-PadJ9)") (class "Default")
      (node (ref "U1") (pin "J9") (pinfunction "VREFN_0_J9") (pintype "passive"))
    )
    (net (code "247") (name "unconnected-(U1-VREFP_0-PadK10)") (class "Default")
      (node (ref "U1") (pin "K10") (pinfunction "VREFP_0_K10") (pintype "passive"))
    )
  )
)
